# fmc.net
KiCad netlist of a schematic drawn in EAGLE
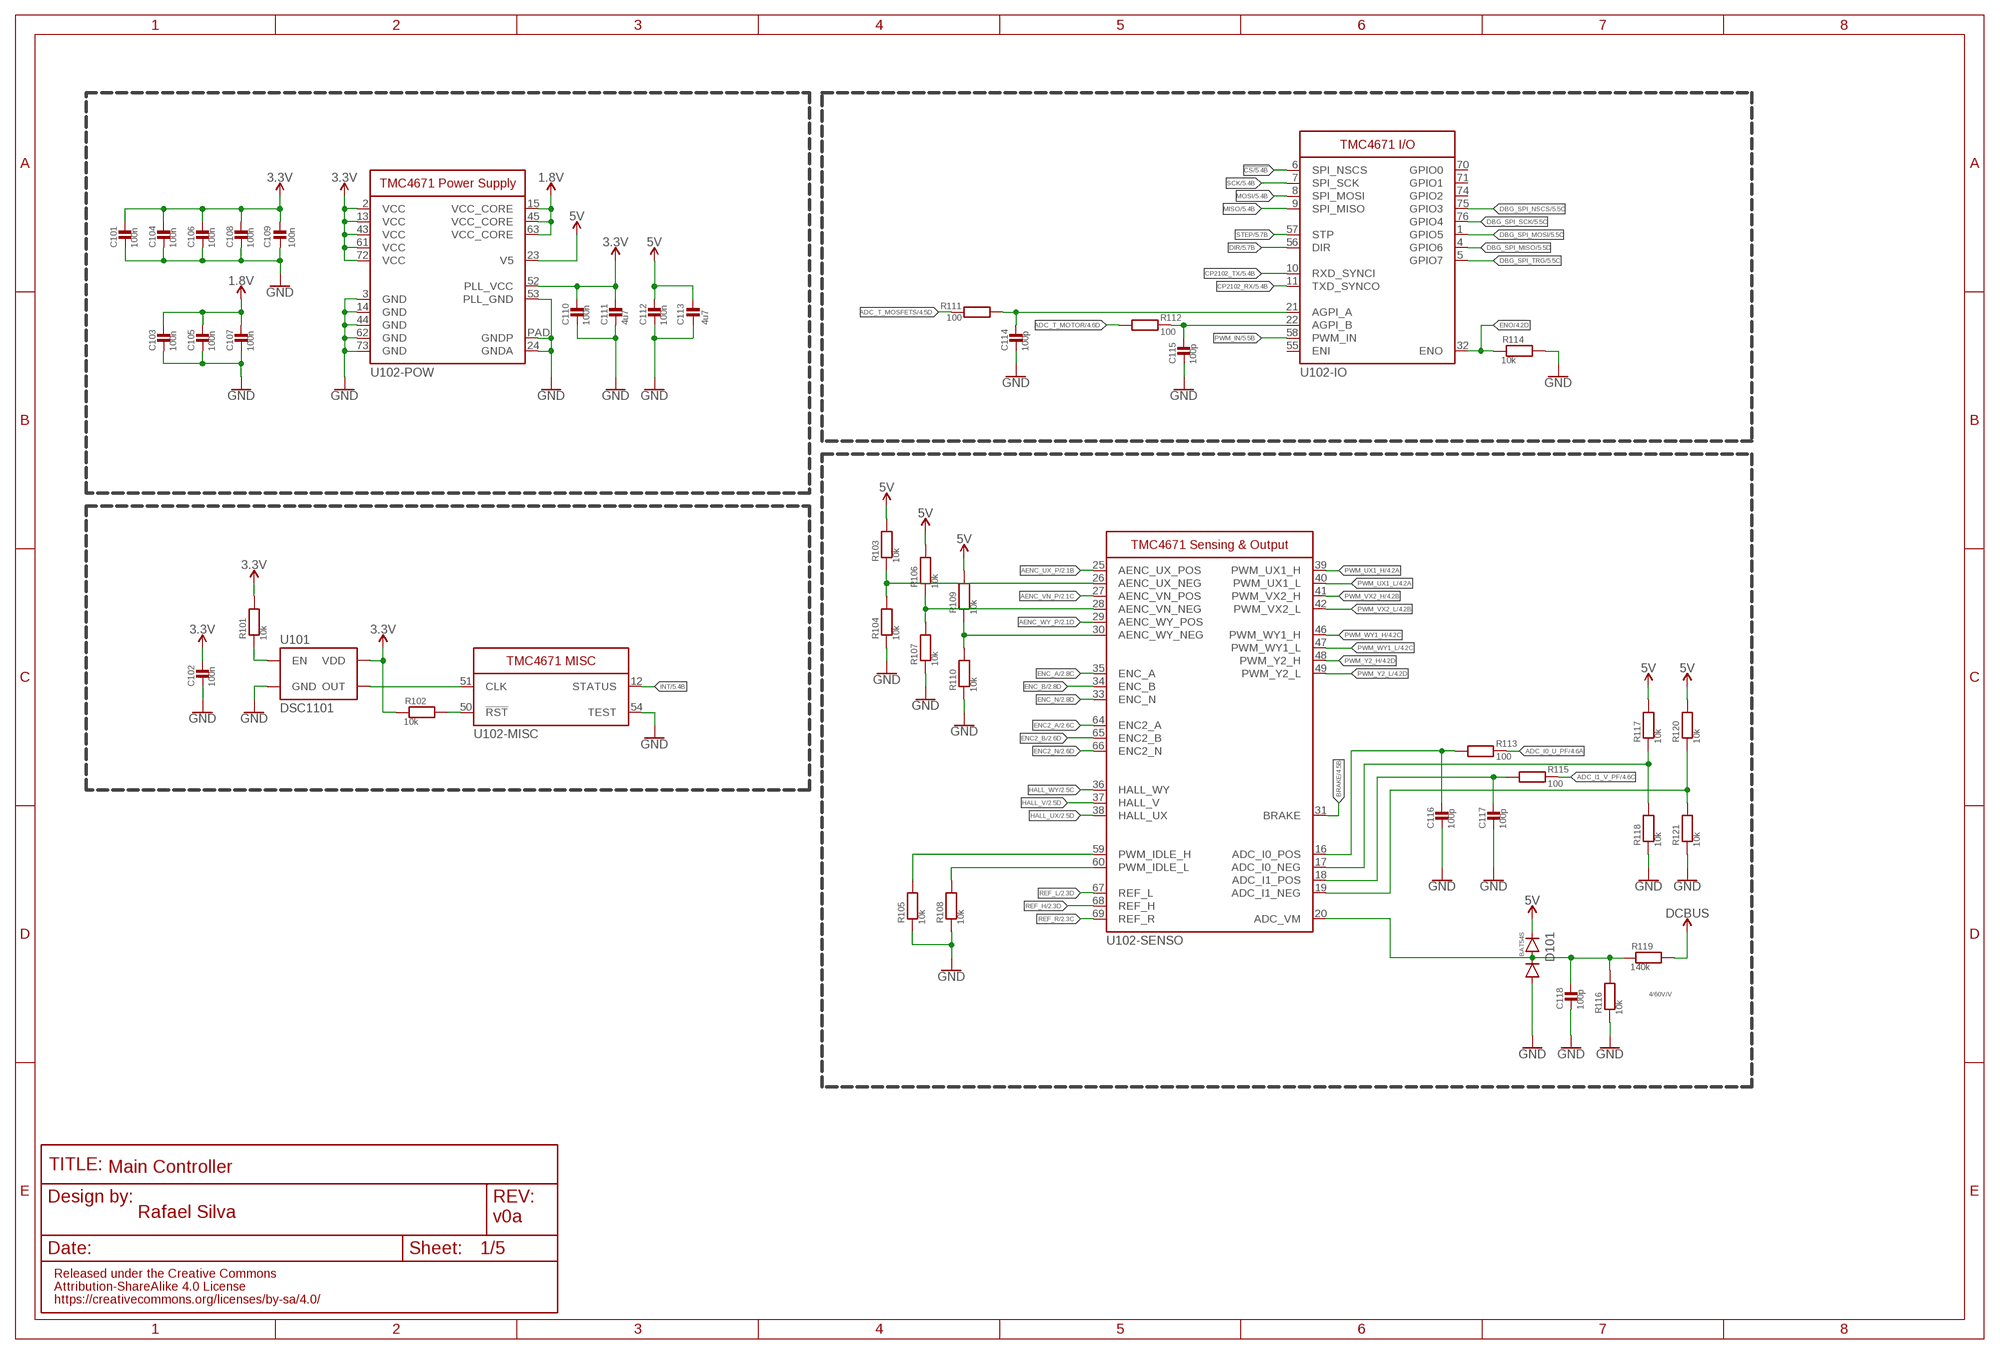
[diagram p0: schematic, sheet 1]
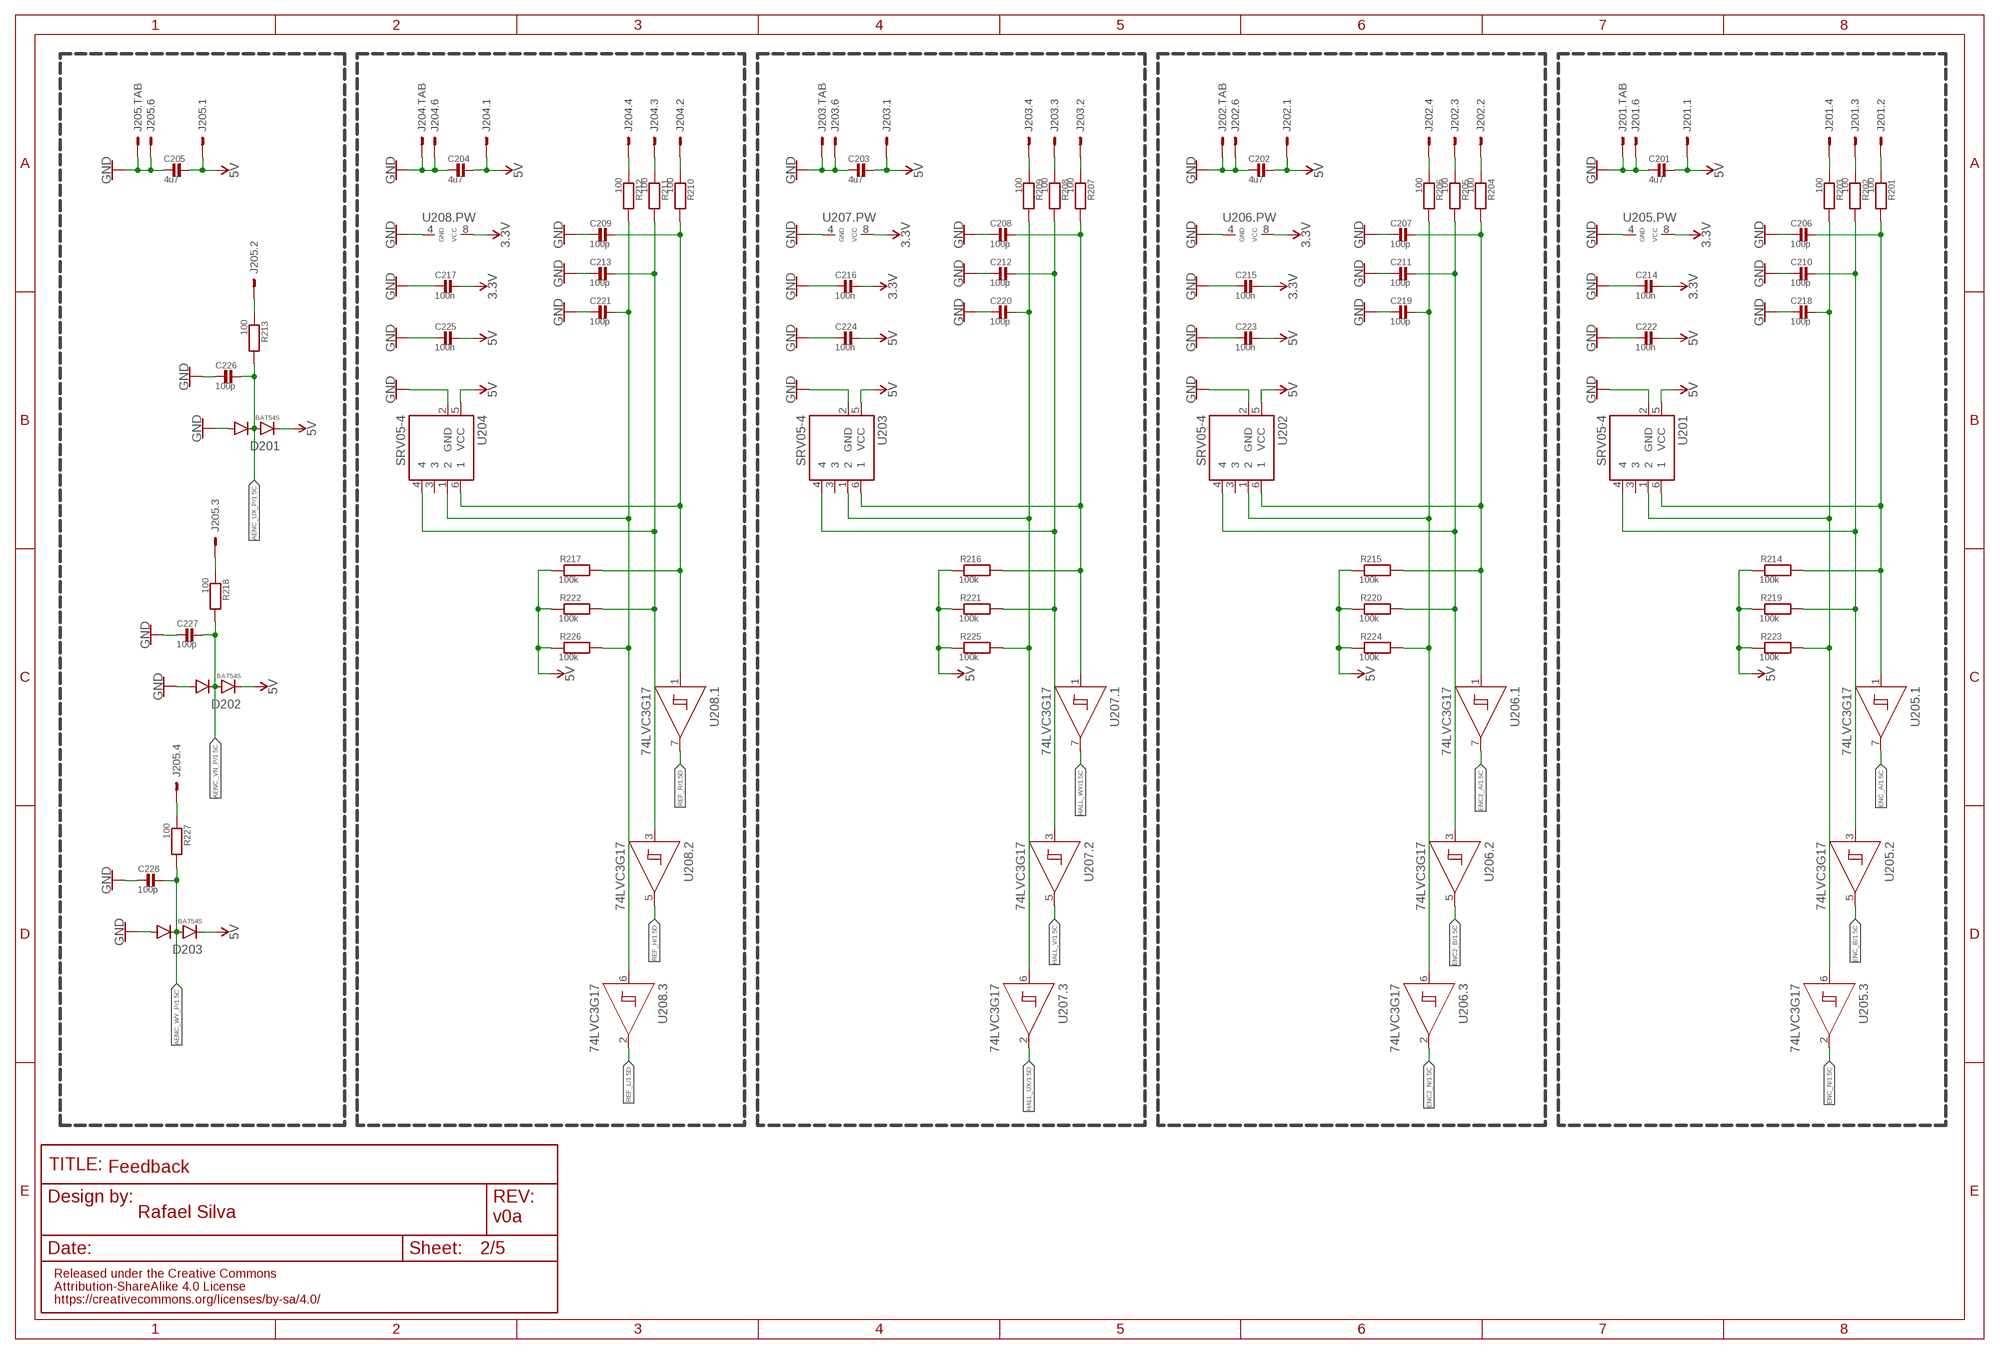
[diagram p1: schematic, sheet 2]
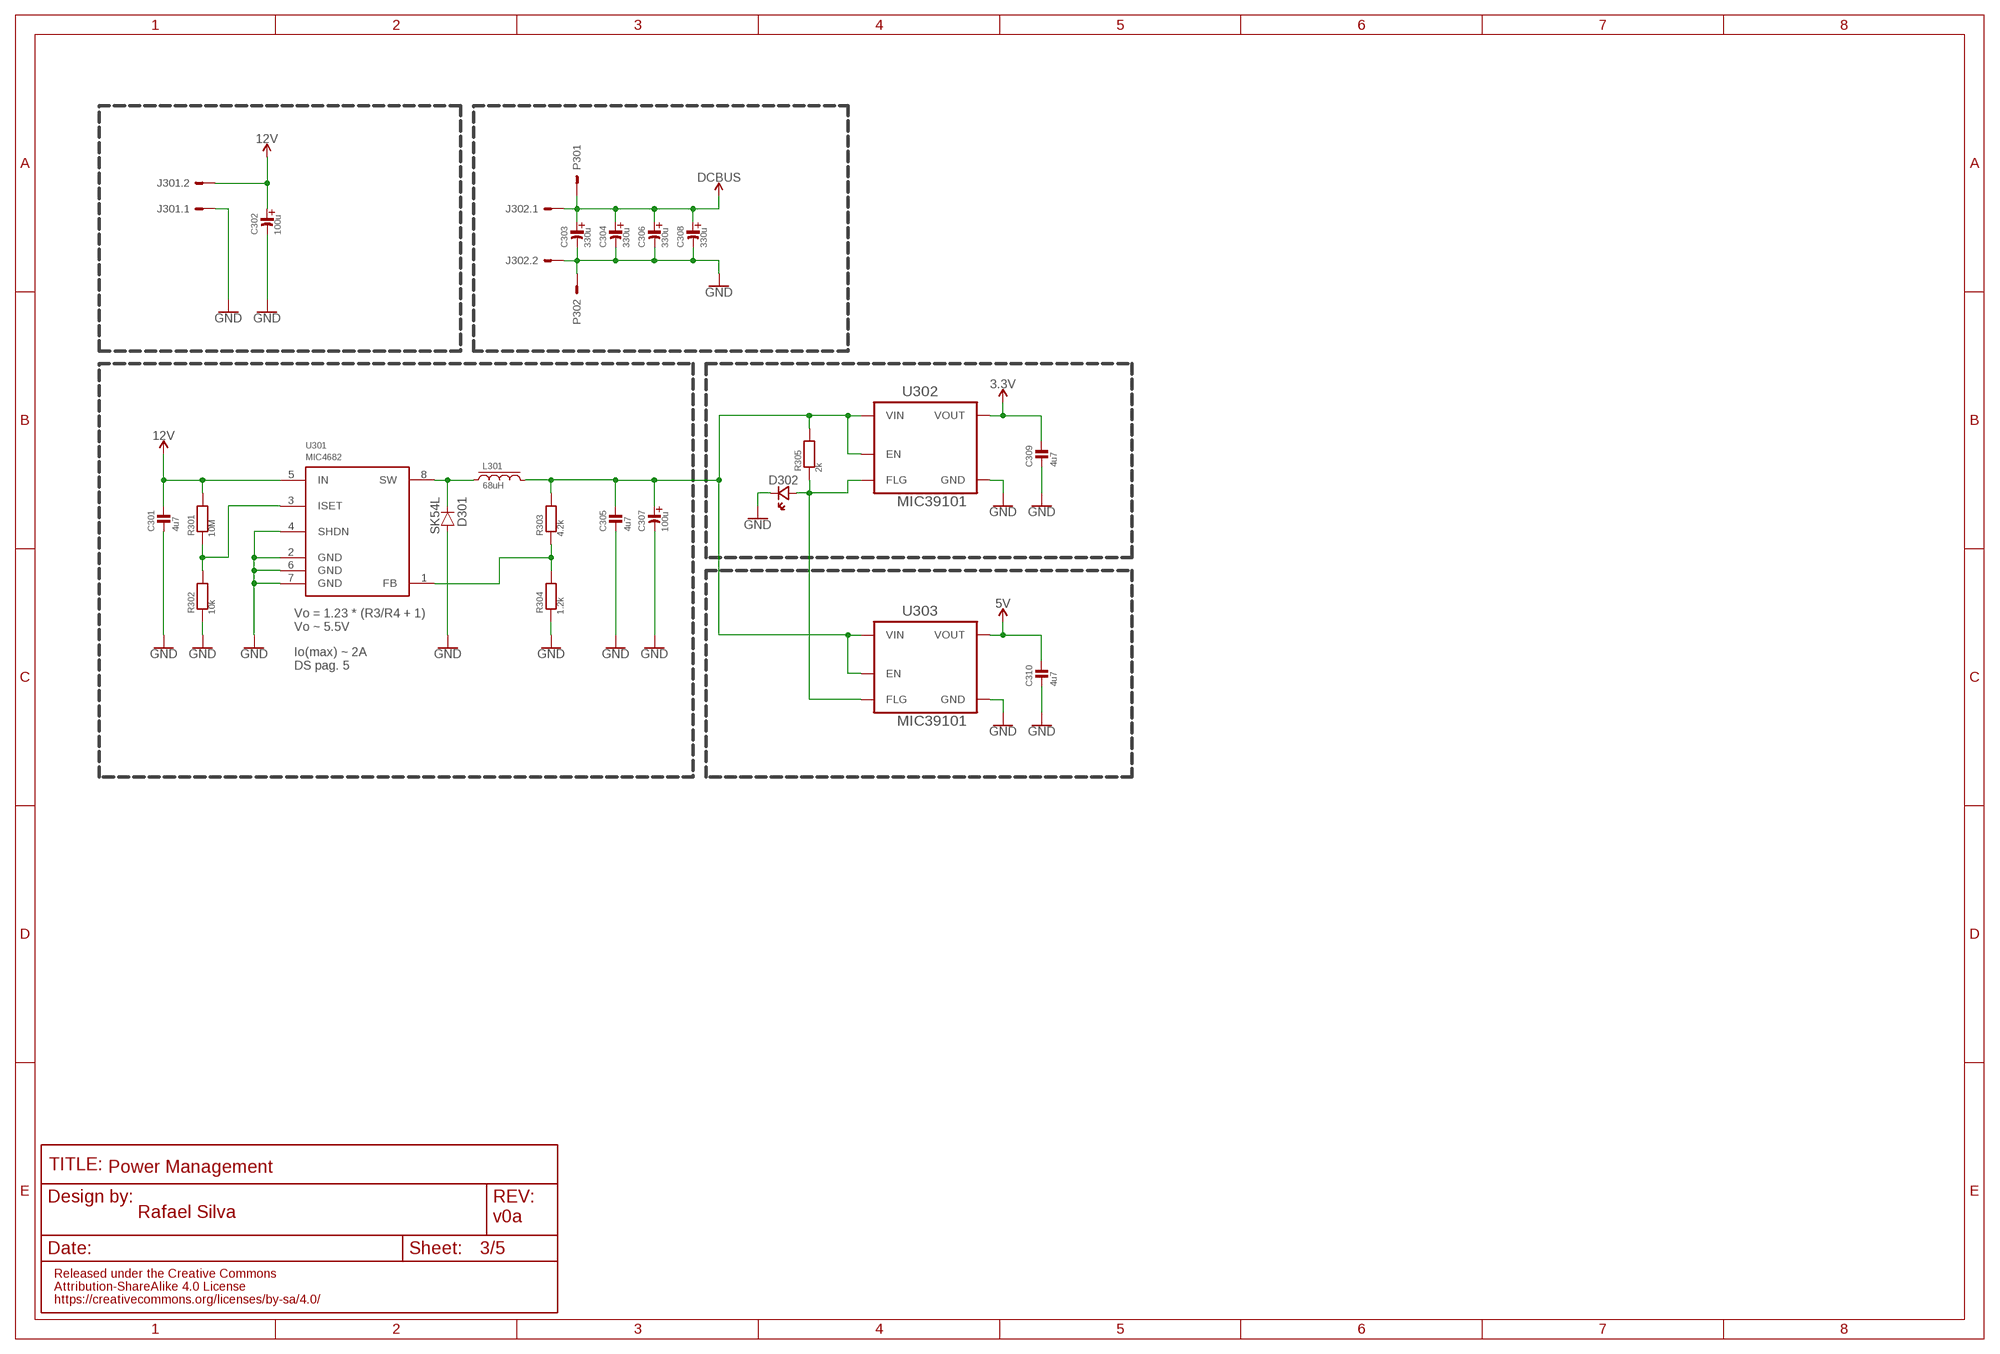
[diagram p2: schematic, sheet 3]
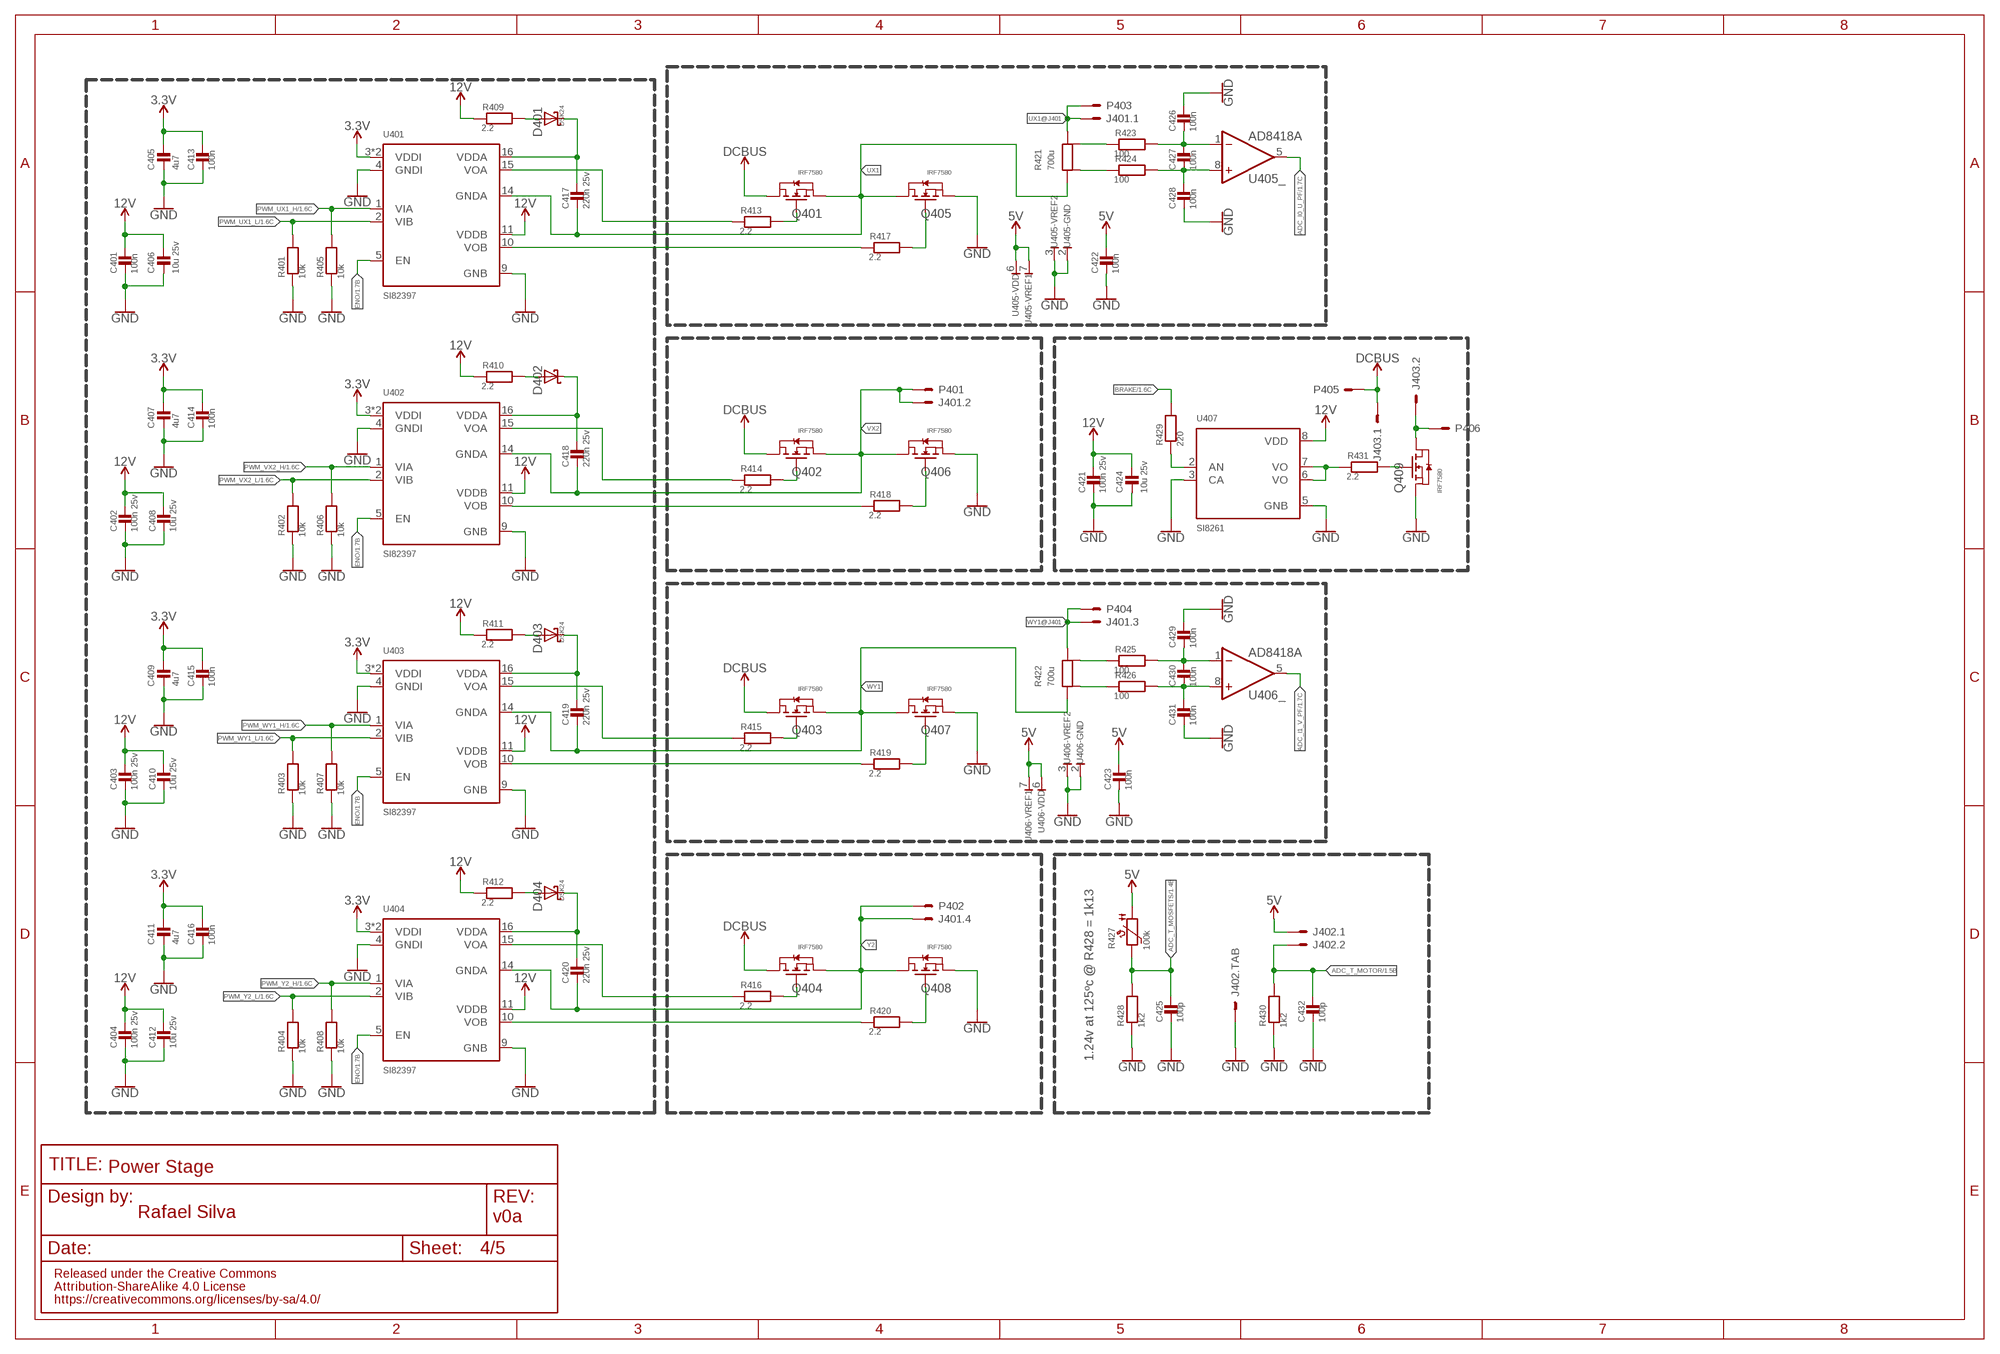
[diagram p3: schematic, sheet 4]
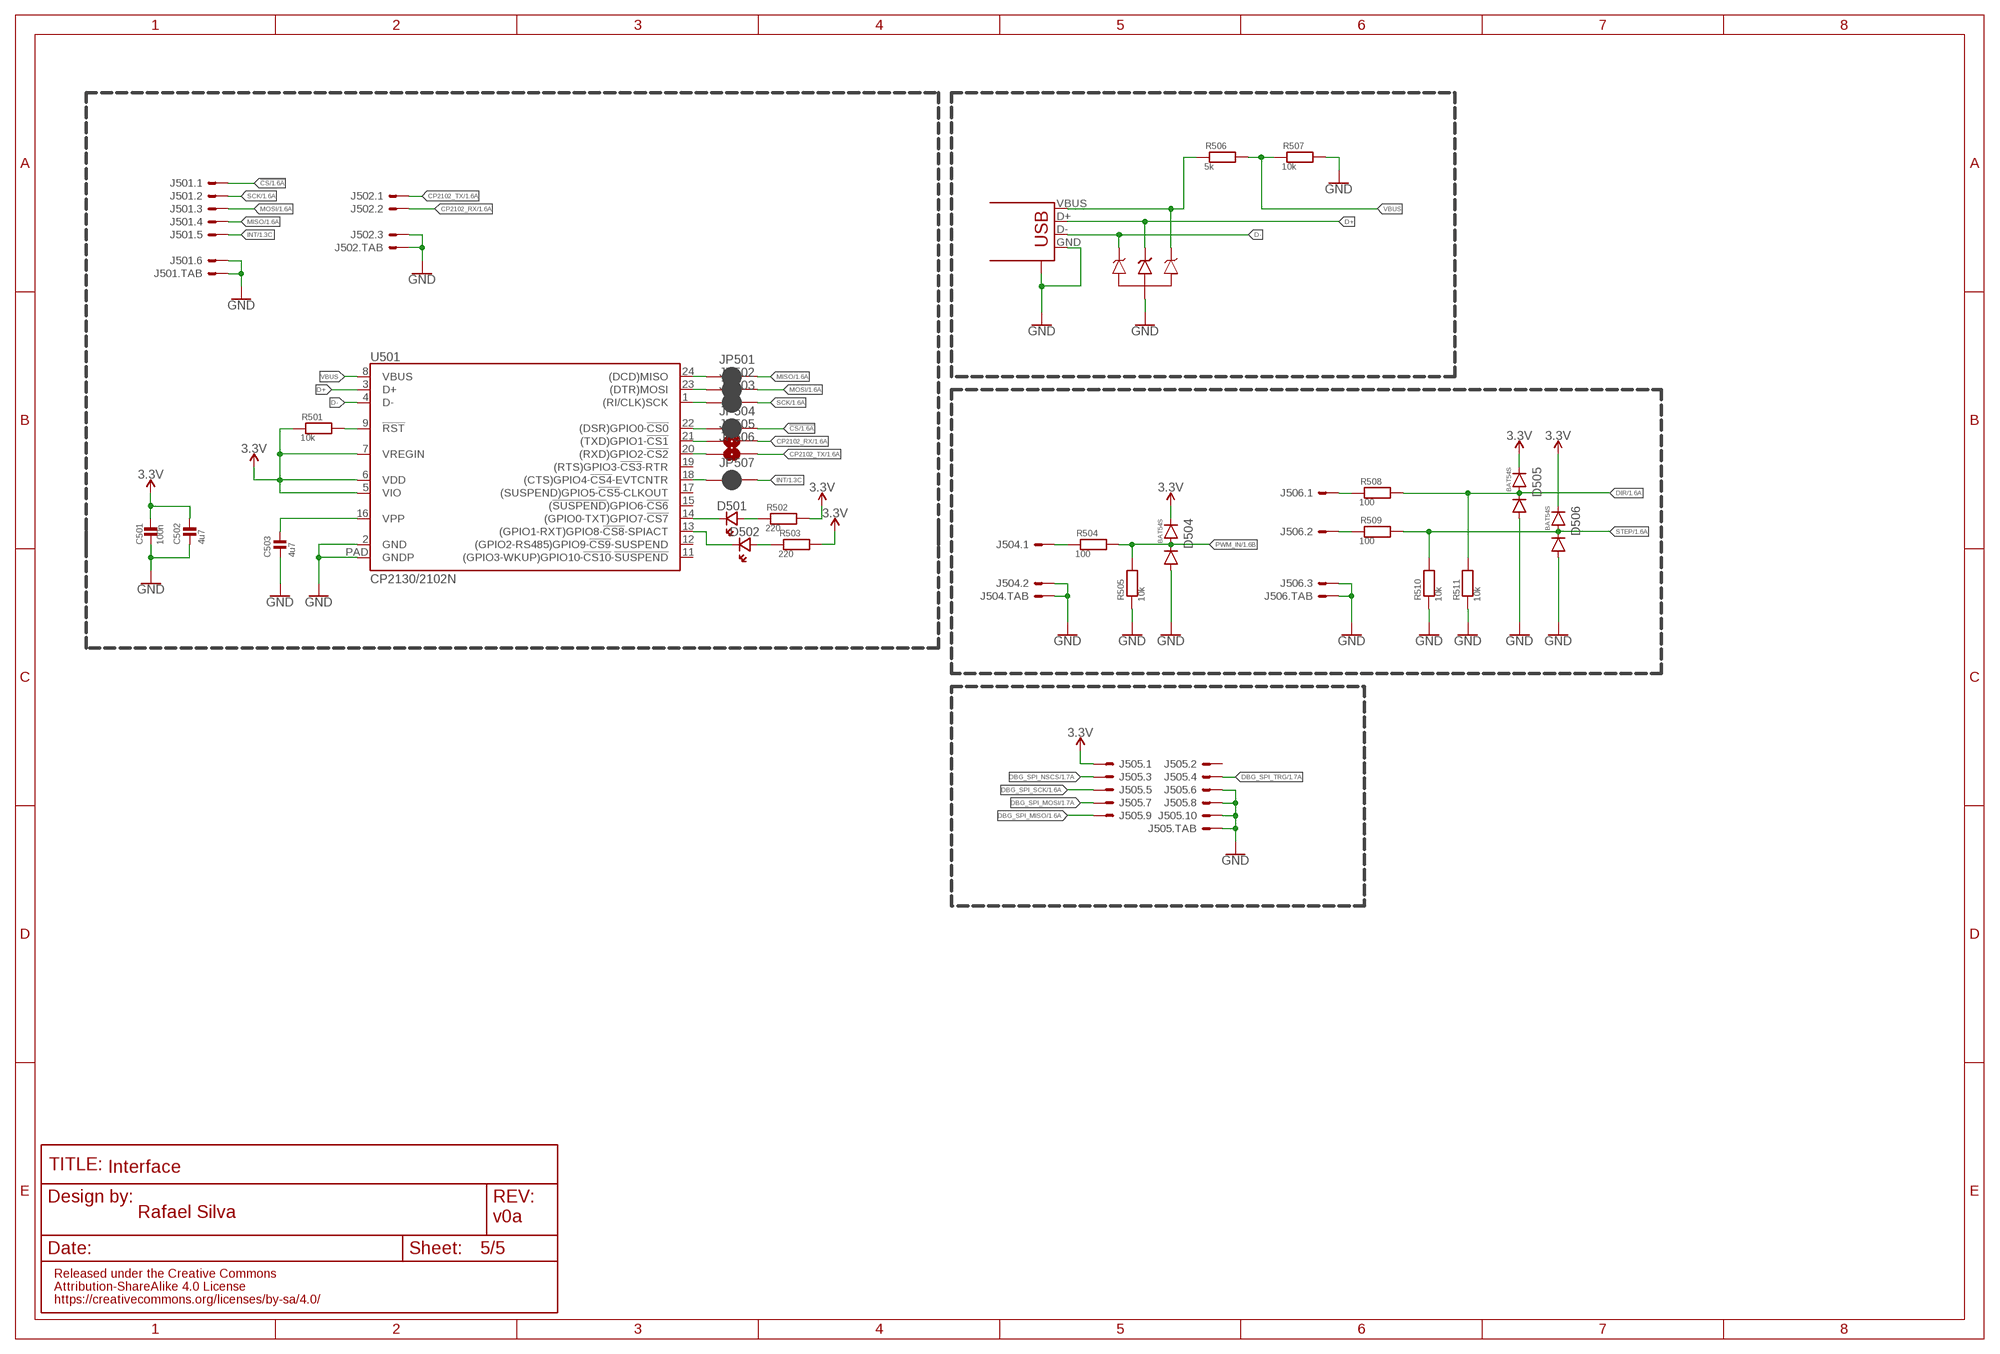
[diagram p4: schematic, sheet 5]

(export (version "E")
  (design (tool "Eeschema 10.0.6"))
  (components
    (comp (ref "C101")
      (value "100n")
      (footprint "eagle-import:0603_WAVE")
      (libsource (lib "eagle-import") (part "MLCC0603"))
    )
    (comp (ref "C102")
      (value "100n")
      (footprint "eagle-import:0603_WAVE")
      (libsource (lib "eagle-import") (part "MLCC0603"))
    )
    (comp (ref "C103")
      (value "100n")
      (footprint "eagle-import:0603_WAVE")
      (libsource (lib "eagle-import") (part "MLCC0603"))
    )
    (comp (ref "C104")
      (value "100n")
      (footprint "eagle-import:0603_WAVE")
      (libsource (lib "eagle-import") (part "MLCC0603"))
    )
    (comp (ref "C105")
      (value "100n")
      (footprint "eagle-import:0603_WAVE")
      (libsource (lib "eagle-import") (part "MLCC0603"))
    )
    (comp (ref "C106")
      (value "100n")
      (footprint "eagle-import:0603_WAVE")
      (libsource (lib "eagle-import") (part "MLCC0603"))
    )
    (comp (ref "C107")
      (value "100n")
      (footprint "eagle-import:0603_WAVE")
      (libsource (lib "eagle-import") (part "MLCC0603"))
    )
    (comp (ref "C108")
      (value "100n")
      (footprint "eagle-import:0603_WAVE")
      (libsource (lib "eagle-import") (part "MLCC0603"))
    )
    (comp (ref "C109")
      (value "100n")
      (footprint "eagle-import:0603_WAVE")
      (libsource (lib "eagle-import") (part "MLCC0603"))
    )
    (comp (ref "C110")
      (value "100n")
      (footprint "eagle-import:0603_WAVE")
      (libsource (lib "eagle-import") (part "MLCC0603"))
    )
    (comp (ref "C111")
      (value "4u7")
      (footprint "eagle-import:0603_WAVE")
      (libsource (lib "eagle-import") (part "MLCC0603"))
    )
    (comp (ref "C112")
      (value "100n")
      (footprint "eagle-import:0603_WAVE")
      (libsource (lib "eagle-import") (part "MLCC0603"))
    )
    (comp (ref "C113")
      (value "4u7")
      (footprint "eagle-import:0603_WAVE")
      (libsource (lib "eagle-import") (part "MLCC0603"))
    )
    (comp (ref "C114")
      (value "100p")
      (footprint "eagle-import:0603_WAVE")
      (libsource (lib "eagle-import") (part "MLCC0603"))
    )
    (comp (ref "C115")
      (value "100p")
      (footprint "eagle-import:0603_WAVE")
      (libsource (lib "eagle-import") (part "MLCC0603"))
    )
    (comp (ref "C116")
      (value "100p")
      (footprint "eagle-import:0603_WAVE")
      (libsource (lib "eagle-import") (part "MLCC0603"))
    )
    (comp (ref "C117")
      (value "100p")
      (footprint "eagle-import:0603_WAVE")
      (libsource (lib "eagle-import") (part "MLCC0603"))
    )
    (comp (ref "C118")
      (value "100p")
      (footprint "eagle-import:0603_WAVE")
      (libsource (lib "eagle-import") (part "MLCC0603"))
    )
    (comp (ref "D101")
      (value "BAT54S")
      (footprint "eagle-import:SOT-23-3")
      (libsource (lib "eagle-import") (part "BAT54S"))
    )
    (comp (ref "R101")
      (value "10k")
      (footprint "eagle-import:0603_WAVE")
      (libsource (lib "eagle-import") (part "RESISTOR0603"))
    )
    (comp (ref "R102")
      (value "10k")
      (footprint "eagle-import:0603_WAVE")
      (libsource (lib "eagle-import") (part "RESISTOR0603"))
    )
    (comp (ref "R103")
      (value "10k")
      (footprint "eagle-import:0603_WAVE")
      (libsource (lib "eagle-import") (part "RESISTOR0603"))
    )
    (comp (ref "R104")
      (value "10k")
      (footprint "eagle-import:0603_WAVE")
      (libsource (lib "eagle-import") (part "RESISTOR0603"))
    )
    (comp (ref "R105")
      (value "10k")
      (footprint "eagle-import:0603_WAVE")
      (libsource (lib "eagle-import") (part "RESISTOR0603"))
    )
    (comp (ref "R106")
      (value "10k")
      (footprint "eagle-import:0603_WAVE")
      (libsource (lib "eagle-import") (part "RESISTOR0603"))
    )
    (comp (ref "R107")
      (value "10k")
      (footprint "eagle-import:0603_WAVE")
      (libsource (lib "eagle-import") (part "RESISTOR0603"))
    )
    (comp (ref "R108")
      (value "10k")
      (footprint "eagle-import:0603_WAVE")
      (libsource (lib "eagle-import") (part "RESISTOR0603"))
    )
    (comp (ref "R109")
      (value "10k")
      (footprint "eagle-import:0603_WAVE")
      (libsource (lib "eagle-import") (part "RESISTOR0603"))
    )
    (comp (ref "R110")
      (value "10k")
      (footprint "eagle-import:0603_WAVE")
      (libsource (lib "eagle-import") (part "RESISTOR0603"))
    )
    (comp (ref "R111")
      (value "100")
      (footprint "eagle-import:0603_WAVE")
      (libsource (lib "eagle-import") (part "RESISTOR0603"))
    )
    (comp (ref "R112")
      (value "100")
      (footprint "eagle-import:0603_WAVE")
      (libsource (lib "eagle-import") (part "RESISTOR0603"))
    )
    (comp (ref "R113")
      (value "100")
      (footprint "eagle-import:0603_WAVE")
      (libsource (lib "eagle-import") (part "RESISTOR0603"))
    )
    (comp (ref "R114")
      (value "10k")
      (footprint "eagle-import:0603_WAVE")
      (libsource (lib "eagle-import") (part "RESISTOR0603"))
    )
    (comp (ref "R115")
      (value "100")
      (footprint "eagle-import:0603_WAVE")
      (libsource (lib "eagle-import") (part "RESISTOR0603"))
    )
    (comp (ref "R116")
      (value "10k")
      (footprint "eagle-import:0603_WAVE")
      (libsource (lib "eagle-import") (part "RESISTOR0603"))
    )
    (comp (ref "R117")
      (value "10k")
      (footprint "eagle-import:0603_WAVE")
      (libsource (lib "eagle-import") (part "RESISTOR0603"))
    )
    (comp (ref "R118")
      (value "10k")
      (footprint "eagle-import:0603_WAVE")
      (libsource (lib "eagle-import") (part "RESISTOR0603"))
    )
    (comp (ref "R119")
      (value "140k")
      (footprint "eagle-import:0603_WAVE")
      (libsource (lib "eagle-import") (part "RESISTOR0603"))
    )
    (comp (ref "R120")
      (value "10k")
      (footprint "eagle-import:0603_WAVE")
      (libsource (lib "eagle-import") (part "RESISTOR0603"))
    )
    (comp (ref "R121")
      (value "10k")
      (footprint "eagle-import:0603_WAVE")
      (libsource (lib "eagle-import") (part "RESISTOR0603"))
    )
    (comp (ref "U101")
      (value "DSC1101")
      (footprint "eagle-import:CDFN_5X3.2")
      (libsource (lib "eagle-import") (part "DSC1101"))
    )
    (comp (ref "U102")
      (value "TMC4671")
      (footprint "eagle-import:QFN76")
      (libsource (lib "eagle-import") (part "TMC4671"))
    )
    (comp (ref "C501")
      (value "100n")
      (footprint "eagle-import:0603_WAVE")
      (libsource (lib "eagle-import") (part "MLCC0603"))
    )
    (comp (ref "C502")
      (value "4u7")
      (footprint "eagle-import:0603_WAVE")
      (libsource (lib "eagle-import") (part "MLCC0603"))
    )
    (comp (ref "C503")
      (value "4u7")
      (footprint "eagle-import:0603_WAVE")
      (libsource (lib "eagle-import") (part "MLCC0603"))
    )
    (comp (ref "D501")
      (value "LED0603")
      (footprint "eagle-import:CHIPLED_0603")
      (libsource (lib "eagle-import") (part "LED0603"))
    )
    (comp (ref "D502")
      (value "LED0603")
      (footprint "eagle-import:CHIPLED_0603")
      (libsource (lib "eagle-import") (part "LED0603"))
    )
    (comp (ref "D503")
      (value "SP0503BAHT")
      (footprint "eagle-import:SOT143")
      (libsource (lib "eagle-import") (part "SP0503BAHT"))
    )
    (comp (ref "D504")
      (value "BAT54S")
      (footprint "eagle-import:SOT-23-3")
      (libsource (lib "eagle-import") (part "BAT54S"))
    )
    (comp (ref "D505")
      (value "BAT54S")
      (footprint "eagle-import:SOT-23-3")
      (libsource (lib "eagle-import") (part "BAT54S"))
    )
    (comp (ref "D506")
      (value "BAT54S")
      (footprint "eagle-import:SOT-23-3")
      (libsource (lib "eagle-import") (part "BAT54S"))
    )
    (comp (ref "J501")
      (value "SH-6")
      (footprint "eagle-import:SM06B-SSR-H-TB")
      (libsource (lib "eagle-import") (part "SH-6"))
    )
    (comp (ref "J502")
      (value "SH-3")
      (footprint "eagle-import:SM03B-SSR-H-TB")
      (libsource (lib "eagle-import") (part "SH-3"))
    )
    (comp (ref "J503")
      (value "USB-SHIELD")
      (footprint "eagle-import:USB-M-S1")
      (libsource (lib "eagle-import") (part "USB-SHIELD"))
    )
    (comp (ref "J504")
      (value "SH-2")
      (footprint "eagle-import:SM02B-SSR-H-TB")
      (libsource (lib "eagle-import") (part "SH-2"))
    )
    (comp (ref "J505")
      (value "F20F-10DP-1V")
      (footprint "eagle-import:F20F-10DP-1V")
      (libsource (lib "eagle-import") (part "F20F-10DP-1V"))
    )
    (comp (ref "J506")
      (value "SH-3")
      (footprint "eagle-import:SM03B-SSR-H-TB")
      (libsource (lib "eagle-import") (part "SH-3"))
    )
    (comp (ref "JP501")
      (value "JUMPER-SMT_2_NC_PASTE_SILK")
      (footprint "eagle-import:SMT-JUMPER_2_NC_PASTE_SILK")
      (libsource (lib "eagle-import") (part "JUMPER-SMT_2_NC_PASTE_SILK"))
    )
    (comp (ref "JP502")
      (value "JUMPER-SMT_2_NC_PASTE_SILK")
      (footprint "eagle-import:SMT-JUMPER_2_NC_PASTE_SILK")
      (libsource (lib "eagle-import") (part "JUMPER-SMT_2_NC_PASTE_SILK"))
    )
    (comp (ref "JP503")
      (value "JUMPER-SMT_2_NC_PASTE_SILK")
      (footprint "eagle-import:SMT-JUMPER_2_NC_PASTE_SILK")
      (libsource (lib "eagle-import") (part "JUMPER-SMT_2_NC_PASTE_SILK"))
    )
    (comp (ref "JP504")
      (value "JUMPER-SMT_2_NC_PASTE_SILK")
      (footprint "eagle-import:SMT-JUMPER_2_NC_PASTE_SILK")
      (libsource (lib "eagle-import") (part "JUMPER-SMT_2_NC_PASTE_SILK"))
    )
    (comp (ref "JP505")
      (value "JUMPER-SMT_2_NO_SILK")
      (footprint "eagle-import:SMT-JUMPER_2_NO_SILK")
      (libsource (lib "eagle-import") (part "JUMPER-SMT_2_NO_SILK"))
    )
    (comp (ref "JP506")
      (value "JUMPER-SMT_2_NO_SILK")
      (footprint "eagle-import:SMT-JUMPER_2_NO_SILK")
      (libsource (lib "eagle-import") (part "JUMPER-SMT_2_NO_SILK"))
    )
    (comp (ref "JP507")
      (value "JUMPER-SMT_2_NC_PASTE_SILK")
      (footprint "eagle-import:SMT-JUMPER_2_NC_PASTE_SILK")
      (libsource (lib "eagle-import") (part "JUMPER-SMT_2_NC_PASTE_SILK"))
    )
    (comp (ref "R501")
      (value "10k")
      (footprint "eagle-import:0603_WAVE")
      (libsource (lib "eagle-import") (part "RESISTOR0603"))
    )
    (comp (ref "R502")
      (value "220")
      (footprint "eagle-import:0603_WAVE")
      (libsource (lib "eagle-import") (part "RESISTOR0603"))
    )
    (comp (ref "R503")
      (value "220")
      (footprint "eagle-import:0603_WAVE")
      (libsource (lib "eagle-import") (part "RESISTOR0603"))
    )
    (comp (ref "R504")
      (value "100")
      (footprint "eagle-import:0603_WAVE")
      (libsource (lib "eagle-import") (part "RESISTOR0603"))
    )
    (comp (ref "R505")
      (value "10k")
      (footprint "eagle-import:0603_WAVE")
      (libsource (lib "eagle-import") (part "RESISTOR0603"))
    )
    (comp (ref "R506")
      (value "5k")
      (footprint "eagle-import:0603_WAVE")
      (libsource (lib "eagle-import") (part "RESISTOR0603"))
    )
    (comp (ref "R507")
      (value "10k")
      (footprint "eagle-import:0603_WAVE")
      (libsource (lib "eagle-import") (part "RESISTOR0603"))
    )
    (comp (ref "R508")
      (value "100")
      (footprint "eagle-import:0603_WAVE")
      (libsource (lib "eagle-import") (part "RESISTOR0603"))
    )
    (comp (ref "R509")
      (value "100")
      (footprint "eagle-import:0603_WAVE")
      (libsource (lib "eagle-import") (part "RESISTOR0603"))
    )
    (comp (ref "R510")
      (value "10k")
      (footprint "eagle-import:0603_WAVE")
      (libsource (lib "eagle-import") (part "RESISTOR0603"))
    )
    (comp (ref "R511")
      (value "10k")
      (footprint "eagle-import:0603_WAVE")
      (libsource (lib "eagle-import") (part "RESISTOR0603"))
    )
    (comp (ref "U501")
      (value "CP2130/2102N")
      (footprint "eagle-import:QFN24")
      (libsource (lib "eagle-import") (part "CP2130/2102N"))
    )
    (comp (ref "C201")
      (value "4u7")
      (footprint "eagle-import:0603_WAVE")
      (libsource (lib "eagle-import") (part "MLCC0603"))
    )
    (comp (ref "C202")
      (value "4u7")
      (footprint "eagle-import:0603_WAVE")
      (libsource (lib "eagle-import") (part "MLCC0603"))
    )
    (comp (ref "C203")
      (value "4u7")
      (footprint "eagle-import:0603_WAVE")
      (libsource (lib "eagle-import") (part "MLCC0603"))
    )
    (comp (ref "C204")
      (value "4u7")
      (footprint "eagle-import:0603_WAVE")
      (libsource (lib "eagle-import") (part "MLCC0603"))
    )
    (comp (ref "C205")
      (value "4u7")
      (footprint "eagle-import:0603_WAVE")
      (libsource (lib "eagle-import") (part "MLCC0603"))
    )
    (comp (ref "C206")
      (value "100p")
      (footprint "eagle-import:0603_WAVE")
      (libsource (lib "eagle-import") (part "MLCC0603"))
    )
    (comp (ref "C207")
      (value "100p")
      (footprint "eagle-import:0603_WAVE")
      (libsource (lib "eagle-import") (part "MLCC0603"))
    )
    (comp (ref "C208")
      (value "100p")
      (footprint "eagle-import:0603_WAVE")
      (libsource (lib "eagle-import") (part "MLCC0603"))
    )
    (comp (ref "C209")
      (value "100p")
      (footprint "eagle-import:0603_WAVE")
      (libsource (lib "eagle-import") (part "MLCC0603"))
    )
    (comp (ref "C210")
      (value "100p")
      (footprint "eagle-import:0603_WAVE")
      (libsource (lib "eagle-import") (part "MLCC0603"))
    )
    (comp (ref "C211")
      (value "100p")
      (footprint "eagle-import:0603_WAVE")
      (libsource (lib "eagle-import") (part "MLCC0603"))
    )
    (comp (ref "C212")
      (value "100p")
      (footprint "eagle-import:0603_WAVE")
      (libsource (lib "eagle-import") (part "MLCC0603"))
    )
    (comp (ref "C213")
      (value "100p")
      (footprint "eagle-import:0603_WAVE")
      (libsource (lib "eagle-import") (part "MLCC0603"))
    )
    (comp (ref "C214")
      (value "100n")
      (footprint "eagle-import:0603_WAVE")
      (libsource (lib "eagle-import") (part "MLCC0603"))
    )
    (comp (ref "C215")
      (value "100n")
      (footprint "eagle-import:0603_WAVE")
      (libsource (lib "eagle-import") (part "MLCC0603"))
    )
    (comp (ref "C216")
      (value "100n")
      (footprint "eagle-import:0603_WAVE")
      (libsource (lib "eagle-import") (part "MLCC0603"))
    )
    (comp (ref "C217")
      (value "100n")
      (footprint "eagle-import:0603_WAVE")
      (libsource (lib "eagle-import") (part "MLCC0603"))
    )
    (comp (ref "C218")
      (value "100p")
      (footprint "eagle-import:0603_WAVE")
      (libsource (lib "eagle-import") (part "MLCC0603"))
    )
    (comp (ref "C219")
      (value "100p")
      (footprint "eagle-import:0603_WAVE")
      (libsource (lib "eagle-import") (part "MLCC0603"))
    )
    (comp (ref "C220")
      (value "100p")
      (footprint "eagle-import:0603_WAVE")
      (libsource (lib "eagle-import") (part "MLCC0603"))
    )
    (comp (ref "C221")
      (value "100p")
      (footprint "eagle-import:0603_WAVE")
      (libsource (lib "eagle-import") (part "MLCC0603"))
    )
    (comp (ref "C222")
      (value "100n")
      (footprint "eagle-import:0603_WAVE")
      (libsource (lib "eagle-import") (part "MLCC0603"))
    )
    (comp (ref "C223")
      (value "100n")
      (footprint "eagle-import:0603_WAVE")
      (libsource (lib "eagle-import") (part "MLCC0603"))
    )
    (comp (ref "C224")
      (value "100n")
      (footprint "eagle-import:0603_WAVE")
      (libsource (lib "eagle-import") (part "MLCC0603"))
    )
    (comp (ref "C225")
      (value "100n")
      (footprint "eagle-import:0603_WAVE")
      (libsource (lib "eagle-import") (part "MLCC0603"))
    )
    (comp (ref "C226")
      (value "100p")
      (footprint "eagle-import:0603_WAVE")
      (libsource (lib "eagle-import") (part "MLCC0603"))
    )
    (comp (ref "C227")
      (value "100p")
      (footprint "eagle-import:0603_WAVE")
      (libsource (lib "eagle-import") (part "MLCC0603"))
    )
    (comp (ref "C228")
      (value "100p")
      (footprint "eagle-import:0603_WAVE")
      (libsource (lib "eagle-import") (part "MLCC0603"))
    )
    (comp (ref "D201")
      (value "BAT54S")
      (footprint "eagle-import:SOT-23-3")
      (libsource (lib "eagle-import") (part "BAT54S"))
    )
    (comp (ref "D202")
      (value "BAT54S")
      (footprint "eagle-import:SOT-23-3")
      (libsource (lib "eagle-import") (part "BAT54S"))
    )
    (comp (ref "D203")
      (value "BAT54S")
      (footprint "eagle-import:SOT-23-3")
      (libsource (lib "eagle-import") (part "BAT54S"))
    )
    (comp (ref "J201")
      (value "SH-5")
      (footprint "eagle-import:SM05B-SSR-H-TB")
      (libsource (lib "eagle-import") (part "SH-5"))
    )
    (comp (ref "J202")
      (value "SH-5")
      (footprint "eagle-import:SM05B-SSR-H-TB")
      (libsource (lib "eagle-import") (part "SH-5"))
    )
    (comp (ref "J203")
      (value "SH-5")
      (footprint "eagle-import:SM05B-SSR-H-TB")
      (libsource (lib "eagle-import") (part "SH-5"))
    )
    (comp (ref "J204")
      (value "SH-5")
      (footprint "eagle-import:SM05B-SSR-H-TB")
      (libsource (lib "eagle-import") (part "SH-5"))
    )
    (comp (ref "J205")
      (value "SH-5")
      (footprint "eagle-import:SM05B-SSR-H-TB")
      (libsource (lib "eagle-import") (part "SH-5"))
    )
    (comp (ref "R201")
      (value "100")
      (footprint "eagle-import:0603_WAVE")
      (libsource (lib "eagle-import") (part "RESISTOR0603"))
    )
    (comp (ref "R202")
      (value "100")
      (footprint "eagle-import:0603_WAVE")
      (libsource (lib "eagle-import") (part "RESISTOR0603"))
    )
    (comp (ref "R203")
      (value "100")
      (footprint "eagle-import:0603_WAVE")
      (libsource (lib "eagle-import") (part "RESISTOR0603"))
    )
    (comp (ref "R204")
      (value "100")
      (footprint "eagle-import:0603_WAVE")
      (libsource (lib "eagle-import") (part "RESISTOR0603"))
    )
    (comp (ref "R205")
      (value "100")
      (footprint "eagle-import:0603_WAVE")
      (libsource (lib "eagle-import") (part "RESISTOR0603"))
    )
    (comp (ref "R206")
      (value "100")
      (footprint "eagle-import:0603_WAVE")
      (libsource (lib "eagle-import") (part "RESISTOR0603"))
    )
    (comp (ref "R207")
      (value "100")
      (footprint "eagle-import:0603_WAVE")
      (libsource (lib "eagle-import") (part "RESISTOR0603"))
    )
    (comp (ref "R208")
      (value "100")
      (footprint "eagle-import:0603_WAVE")
      (libsource (lib "eagle-import") (part "RESISTOR0603"))
    )
    (comp (ref "R209")
      (value "100")
      (footprint "eagle-import:0603_WAVE")
      (libsource (lib "eagle-import") (part "RESISTOR0603"))
    )
    (comp (ref "R210")
      (value "100")
      (footprint "eagle-import:0603_WAVE")
      (libsource (lib "eagle-import") (part "RESISTOR0603"))
    )
    (comp (ref "R211")
      (value "100")
      (footprint "eagle-import:0603_WAVE")
      (libsource (lib "eagle-import") (part "RESISTOR0603"))
    )
    (comp (ref "R212")
      (value "100")
      (footprint "eagle-import:0603_WAVE")
      (libsource (lib "eagle-import") (part "RESISTOR0603"))
    )
    (comp (ref "R213")
      (value "100")
      (footprint "eagle-import:0603_WAVE")
      (libsource (lib "eagle-import") (part "RESISTOR0603"))
    )
    (comp (ref "R214")
      (value "100k")
      (footprint "eagle-import:0603_WAVE")
      (libsource (lib "eagle-import") (part "RESISTOR0603"))
    )
    (comp (ref "R215")
      (value "100k")
      (footprint "eagle-import:0603_WAVE")
      (libsource (lib "eagle-import") (part "RESISTOR0603"))
    )
    (comp (ref "R216")
      (value "100k")
      (footprint "eagle-import:0603_WAVE")
      (libsource (lib "eagle-import") (part "RESISTOR0603"))
    )
    (comp (ref "R217")
      (value "100k")
      (footprint "eagle-import:0603_WAVE")
      (libsource (lib "eagle-import") (part "RESISTOR0603"))
    )
    (comp (ref "R218")
      (value "100")
      (footprint "eagle-import:0603_WAVE")
      (libsource (lib "eagle-import") (part "RESISTOR0603"))
    )
    (comp (ref "R219")
      (value "100k")
      (footprint "eagle-import:0603_WAVE")
      (libsource (lib "eagle-import") (part "RESISTOR0603"))
    )
    (comp (ref "R220")
      (value "100k")
      (footprint "eagle-import:0603_WAVE")
      (libsource (lib "eagle-import") (part "RESISTOR0603"))
    )
    (comp (ref "R221")
      (value "100k")
      (footprint "eagle-import:0603_WAVE")
      (libsource (lib "eagle-import") (part "RESISTOR0603"))
    )
    (comp (ref "R222")
      (value "100k")
      (footprint "eagle-import:0603_WAVE")
      (libsource (lib "eagle-import") (part "RESISTOR0603"))
    )
    (comp (ref "R223")
      (value "100k")
      (footprint "eagle-import:0603_WAVE")
      (libsource (lib "eagle-import") (part "RESISTOR0603"))
    )
    (comp (ref "R224")
      (value "100k")
      (footprint "eagle-import:0603_WAVE")
      (libsource (lib "eagle-import") (part "RESISTOR0603"))
    )
    (comp (ref "R225")
      (value "100k")
      (footprint "eagle-import:0603_WAVE")
      (libsource (lib "eagle-import") (part "RESISTOR0603"))
    )
    (comp (ref "R226")
      (value "100k")
      (footprint "eagle-import:0603_WAVE")
      (libsource (lib "eagle-import") (part "RESISTOR0603"))
    )
    (comp (ref "R227")
      (value "100")
      (footprint "eagle-import:0603_WAVE")
      (libsource (lib "eagle-import") (part "RESISTOR0603"))
    )
    (comp (ref "U201")
      (value "SRV05-4")
      (footprint "eagle-import:SOT23-6")
      (libsource (lib "eagle-import") (part "SRV05-4"))
    )
    (comp (ref "U202")
      (value "SRV05-4")
      (footprint "eagle-import:SOT23-6")
      (libsource (lib "eagle-import") (part "SRV05-4"))
    )
    (comp (ref "U203")
      (value "SRV05-4")
      (footprint "eagle-import:SOT23-6")
      (libsource (lib "eagle-import") (part "SRV05-4"))
    )
    (comp (ref "U204")
      (value "SRV05-4")
      (footprint "eagle-import:SOT23-6")
      (libsource (lib "eagle-import") (part "SRV05-4"))
    )
    (comp (ref "U205")
      (value "74LVC3G17")
      (footprint "eagle-import:TSSOP-8")
      (libsource (lib "eagle-import") (part "74LVC3G17"))
    )
    (comp (ref "U206")
      (value "74LVC3G17")
      (footprint "eagle-import:TSSOP-8")
      (libsource (lib "eagle-import") (part "74LVC3G17"))
    )
    (comp (ref "U207")
      (value "74LVC3G17")
      (footprint "eagle-import:TSSOP-8")
      (libsource (lib "eagle-import") (part "74LVC3G17"))
    )
    (comp (ref "U208")
      (value "74LVC3G17")
      (footprint "eagle-import:TSSOP-8")
      (libsource (lib "eagle-import") (part "74LVC3G17"))
    )
    (comp (ref "C401")
      (value "100n")
      (footprint "eagle-import:0603_WAVE")
      (libsource (lib "eagle-import") (part "MLCC0603"))
    )
    (comp (ref "C402")
      (value "100n 25v")
      (footprint "eagle-import:0603_WAVE")
      (libsource (lib "eagle-import") (part "MLCC0603"))
    )
    (comp (ref "C403")
      (value "100n 25v")
      (footprint "eagle-import:0603_WAVE")
      (libsource (lib "eagle-import") (part "MLCC0603"))
    )
    (comp (ref "C404")
      (value "100n 25v")
      (footprint "eagle-import:0603_WAVE")
      (libsource (lib "eagle-import") (part "MLCC0603"))
    )
    (comp (ref "C405")
      (value "4u7")
      (footprint "eagle-import:0603_WAVE")
      (libsource (lib "eagle-import") (part "MLCC0603"))
    )
    (comp (ref "C406")
      (value "10u 25v")
      (footprint "eagle-import:0603_WAVE")
      (libsource (lib "eagle-import") (part "MLCC0603"))
    )
    (comp (ref "C407")
      (value "4u7")
      (footprint "eagle-import:0603_WAVE")
      (libsource (lib "eagle-import") (part "MLCC0603"))
    )
    (comp (ref "C408")
      (value "10u 25v")
      (footprint "eagle-import:0603_WAVE")
      (libsource (lib "eagle-import") (part "MLCC0603"))
    )
    (comp (ref "C409")
      (value "4u7")
      (footprint "eagle-import:0603_WAVE")
      (libsource (lib "eagle-import") (part "MLCC0603"))
    )
    (comp (ref "C410")
      (value "10u 25v")
      (footprint "eagle-import:0603_WAVE")
      (libsource (lib "eagle-import") (part "MLCC0603"))
    )
    (comp (ref "C411")
      (value "4u7")
      (footprint "eagle-import:0603_WAVE")
      (libsource (lib "eagle-import") (part "MLCC0603"))
    )
    (comp (ref "C412")
      (value "10u 25v")
      (footprint "eagle-import:0603_WAVE")
      (libsource (lib "eagle-import") (part "MLCC0603"))
    )
    (comp (ref "C413")
      (value "100n")
      (footprint "eagle-import:0603_WAVE")
      (libsource (lib "eagle-import") (part "MLCC0603"))
    )
    (comp (ref "C414")
      (value "100n")
      (footprint "eagle-import:0603_WAVE")
      (libsource (lib "eagle-import") (part "MLCC0603"))
    )
    (comp (ref "C415")
      (value "100n")
      (footprint "eagle-import:0603_WAVE")
      (libsource (lib "eagle-import") (part "MLCC0603"))
    )
    (comp (ref "C416")
      (value "100n")
      (footprint "eagle-import:0603_WAVE")
      (libsource (lib "eagle-import") (part "MLCC0603"))
    )
    (comp (ref "C417")
      (value "220n 25v")
      (footprint "eagle-import:0603_WAVE")
      (libsource (lib "eagle-import") (part "MLCC0603"))
    )
    (comp (ref "C418")
      (value "220n 25v")
      (footprint "eagle-import:0603_WAVE")
      (libsource (lib "eagle-import") (part "MLCC0603"))
    )
    (comp (ref "C419")
      (value "220n 25v")
      (footprint "eagle-import:0603_WAVE")
      (libsource (lib "eagle-import") (part "MLCC0603"))
    )
    (comp (ref "C420")
      (value "220n 25v")
      (footprint "eagle-import:0603_WAVE")
      (libsource (lib "eagle-import") (part "MLCC0603"))
    )
    (comp (ref "C421")
      (value "100n 25v")
      (footprint "eagle-import:0603_WAVE")
      (libsource (lib "eagle-import") (part "MLCC0603"))
    )
    (comp (ref "C422")
      (value "100n")
      (footprint "eagle-import:0603_WAVE")
      (libsource (lib "eagle-import") (part "MLCC0603"))
    )
    (comp (ref "C423")
      (value "100n")
      (footprint "eagle-import:0603_WAVE")
      (libsource (lib "eagle-import") (part "MLCC0603"))
    )
    (comp (ref "C424")
      (value "10u 25v")
      (footprint "eagle-import:0603_WAVE")
      (libsource (lib "eagle-import") (part "MLCC0603"))
    )
    (comp (ref "C425")
      (value "100p")
      (footprint "eagle-import:0603_WAVE")
      (libsource (lib "eagle-import") (part "MLCC0603"))
    )
    (comp (ref "C426")
      (value "100n")
      (footprint "eagle-import:0603_WAVE")
      (libsource (lib "eagle-import") (part "MLCC0603"))
    )
    (comp (ref "C427")
      (value "100n")
      (footprint "eagle-import:0603_WAVE")
      (libsource (lib "eagle-import") (part "MLCC0603"))
    )
    (comp (ref "C428")
      (value "100n")
      (footprint "eagle-import:0603_WAVE")
      (libsource (lib "eagle-import") (part "MLCC0603"))
    )
    (comp (ref "C429")
      (value "100n")
      (footprint "eagle-import:0603_WAVE")
      (libsource (lib "eagle-import") (part "MLCC0603"))
    )
    (comp (ref "C430")
      (value "100n")
      (footprint "eagle-import:0603_WAVE")
      (libsource (lib "eagle-import") (part "MLCC0603"))
    )
    (comp (ref "C431")
      (value "100n")
      (footprint "eagle-import:0603_WAVE")
      (libsource (lib "eagle-import") (part "MLCC0603"))
    )
    (comp (ref "C432")
      (value "100p")
      (footprint "eagle-import:0603_WAVE")
      (libsource (lib "eagle-import") (part "MLCC0603"))
    )
    (comp (ref "D401")
      (value "DSK24")
      (footprint "eagle-import:SOD-123")
      (libsource (lib "eagle-import") (part "DSK24"))
    )
    (comp (ref "D402")
      (value "DSK24")
      (footprint "eagle-import:SOD-123")
      (libsource (lib "eagle-import") (part "DSK24"))
    )
    (comp (ref "D403")
      (value "DSK24")
      (footprint "eagle-import:SOD-123")
      (libsource (lib "eagle-import") (part "DSK24"))
    )
    (comp (ref "D404")
      (value "DSK24")
      (footprint "eagle-import:SOD-123")
      (libsource (lib "eagle-import") (part "DSK24"))
    )
    (comp (ref "J401")
      (value "4P-6.35P")
      (footprint "eagle-import:4P-6.35P")
      (libsource (lib "eagle-import") (part "4P-6.35P"))
    )
    (comp (ref "J402")
      (value "SH-2")
      (footprint "eagle-import:SM02B-SSR-H-TB")
      (libsource (lib "eagle-import") (part "SH-2"))
    )
    (comp (ref "J403")
      (value "2P-6.35P")
      (footprint "eagle-import:2P-6.35P")
      (libsource (lib "eagle-import") (part "2P-6.35P"))
    )
    (comp (ref "P401")
      (value "POWPAD")
      (footprint "eagle-import:TH-HP")
      (libsource (lib "eagle-import") (part "POWPAD"))
    )
    (comp (ref "P402")
      (value "POWPAD")
      (footprint "eagle-import:TH-HP")
      (libsource (lib "eagle-import") (part "POWPAD"))
    )
    (comp (ref "P403")
      (value "POWPAD")
      (footprint "eagle-import:TH-HP")
      (libsource (lib "eagle-import") (part "POWPAD"))
    )
    (comp (ref "P404")
      (value "POWPAD")
      (footprint "eagle-import:TH-HP")
      (libsource (lib "eagle-import") (part "POWPAD"))
    )
    (comp (ref "P405")
      (value "POWPAD")
      (footprint "eagle-import:TH-HP")
      (libsource (lib "eagle-import") (part "POWPAD"))
    )
    (comp (ref "P406")
      (value "POWPAD")
      (footprint "eagle-import:TH-HP")
      (libsource (lib "eagle-import") (part "POWPAD"))
    )
    (comp (ref "Q401")
      (value "IRF7580")
      (footprint "eagle-import:DIRECTFET-ME")
      (libsource (lib "eagle-import") (part "IRF7580"))
    )
    (comp (ref "Q402")
      (value "IRF7580")
      (footprint "eagle-import:DIRECTFET-ME")
      (libsource (lib "eagle-import") (part "IRF7580"))
    )
    (comp (ref "Q403")
      (value "IRF7580")
      (footprint "eagle-import:DIRECTFET-ME")
      (libsource (lib "eagle-import") (part "IRF7580"))
    )
    (comp (ref "Q404")
      (value "IRF7580")
      (footprint "eagle-import:DIRECTFET-ME")
      (libsource (lib "eagle-import") (part "IRF7580"))
    )
    (comp (ref "Q405")
      (value "IRF7580")
      (footprint "eagle-import:DIRECTFET-ME")
      (libsource (lib "eagle-import") (part "IRF7580"))
    )
    (comp (ref "Q406")
      (value "IRF7580")
      (footprint "eagle-import:DIRECTFET-ME")
      (libsource (lib "eagle-import") (part "IRF7580"))
    )
    (comp (ref "Q407")
      (value "IRF7580")
      (footprint "eagle-import:DIRECTFET-ME")
      (libsource (lib "eagle-import") (part "IRF7580"))
    )
    (comp (ref "Q408")
      (value "IRF7580")
      (footprint "eagle-import:DIRECTFET-ME")
      (libsource (lib "eagle-import") (part "IRF7580"))
    )
    (comp (ref "Q409")
      (value "IRF7580")
      (footprint "eagle-import:DIRECTFET-ME")
      (libsource (lib "eagle-import") (part "IRF7580"))
    )
    (comp (ref "R401")
      (value "10k")
      (footprint "eagle-import:0603_WAVE")
      (libsource (lib "eagle-import") (part "RESISTOR0603"))
    )
    (comp (ref "R402")
      (value "10k")
      (footprint "eagle-import:0603_WAVE")
      (libsource (lib "eagle-import") (part "RESISTOR0603"))
    )
    (comp (ref "R403")
      (value "10k")
      (footprint "eagle-import:0603_WAVE")
      (libsource (lib "eagle-import") (part "RESISTOR0603"))
    )
    (comp (ref "R404")
      (value "10k")
      (footprint "eagle-import:0603_WAVE")
      (libsource (lib "eagle-import") (part "RESISTOR0603"))
    )
    (comp (ref "R405")
      (value "10k")
      (footprint "eagle-import:0603_WAVE")
      (libsource (lib "eagle-import") (part "RESISTOR0603"))
    )
    (comp (ref "R406")
      (value "10k")
      (footprint "eagle-import:0603_WAVE")
      (libsource (lib "eagle-import") (part "RESISTOR0603"))
    )
    (comp (ref "R407")
      (value "10k")
      (footprint "eagle-import:0603_WAVE")
      (libsource (lib "eagle-import") (part "RESISTOR0603"))
    )
    (comp (ref "R408")
      (value "10k")
      (footprint "eagle-import:0603_WAVE")
      (libsource (lib "eagle-import") (part "RESISTOR0603"))
    )
    (comp (ref "R409")
      (value "2.2")
      (footprint "eagle-import:0603_WAVE")
      (libsource (lib "eagle-import") (part "RESISTOR0603"))
    )
    (comp (ref "R410")
      (value "2.2")
      (footprint "eagle-import:0603_WAVE")
      (libsource (lib "eagle-import") (part "RESISTOR0603"))
    )
    (comp (ref "R411")
      (value "2.2")
      (footprint "eagle-import:0603_WAVE")
      (libsource (lib "eagle-import") (part "RESISTOR0603"))
    )
    (comp (ref "R412")
      (value "2.2")
      (footprint "eagle-import:0603_WAVE")
      (libsource (lib "eagle-import") (part "RESISTOR0603"))
    )
    (comp (ref "R413")
      (value "2.2")
      (footprint "eagle-import:0603_WAVE")
      (libsource (lib "eagle-import") (part "RESISTOR0603"))
    )
    (comp (ref "R414")
      (value "2.2")
      (footprint "eagle-import:0603_WAVE")
      (libsource (lib "eagle-import") (part "RESISTOR0603"))
    )
    (comp (ref "R415")
      (value "2.2")
      (footprint "eagle-import:0603_WAVE")
      (libsource (lib "eagle-import") (part "RESISTOR0603"))
    )
    (comp (ref "R416")
      (value "2.2")
      (footprint "eagle-import:0603_WAVE")
      (libsource (lib "eagle-import") (part "RESISTOR0603"))
    )
    (comp (ref "R417")
      (value "2.2")
      (footprint "eagle-import:0603_WAVE")
      (libsource (lib "eagle-import") (part "RESISTOR0603"))
    )
    (comp (ref "R418")
      (value "2.2")
      (footprint "eagle-import:0603_WAVE")
      (libsource (lib "eagle-import") (part "RESISTOR0603"))
    )
    (comp (ref "R419")
      (value "2.2")
      (footprint "eagle-import:0603_WAVE")
      (libsource (lib "eagle-import") (part "RESISTOR0603"))
    )
    (comp (ref "R420")
      (value "2.2")
      (footprint "eagle-import:0603_WAVE")
      (libsource (lib "eagle-import") (part "RESISTOR0603"))
    )
    (comp (ref "R421")
      (value "700u")
      (footprint "eagle-import:3920")
      (libsource (lib "eagle-import") (part "LRMAP3920"))
    )
    (comp (ref "R422")
      (value "700u")
      (footprint "eagle-import:3920")
      (libsource (lib "eagle-import") (part "LRMAP3920"))
    )
    (comp (ref "R423")
      (value "100")
      (footprint "eagle-import:0603_WAVE")
      (libsource (lib "eagle-import") (part "RESISTOR0603"))
    )
    (comp (ref "R424")
      (value "100")
      (footprint "eagle-import:0603_WAVE")
      (libsource (lib "eagle-import") (part "RESISTOR0603"))
    )
    (comp (ref "R425")
      (value "100")
      (footprint "eagle-import:0603_WAVE")
      (libsource (lib "eagle-import") (part "RESISTOR0603"))
    )
    (comp (ref "R426")
      (value "100")
      (footprint "eagle-import:0603_WAVE")
      (libsource (lib "eagle-import") (part "RESISTOR0603"))
    )
    (comp (ref "R427")
      (value "100k")
      (footprint "eagle-import:0603_WAVE")
      (libsource (lib "eagle-import") (part "NTC0603"))
    )
    (comp (ref "R428")
      (value "1k2")
      (footprint "eagle-import:0603_WAVE")
      (libsource (lib "eagle-import") (part "RESISTOR0603"))
    )
    (comp (ref "R429")
      (value "220")
      (footprint "eagle-import:0603_WAVE")
      (libsource (lib "eagle-import") (part "RESISTOR0603"))
    )
    (comp (ref "R430")
      (value "1k2")
      (footprint "eagle-import:0603_WAVE")
      (libsource (lib "eagle-import") (part "RESISTOR0603"))
    )
    (comp (ref "R431")
      (value "2.2")
      (footprint "eagle-import:0603_WAVE")
      (libsource (lib "eagle-import") (part "RESISTOR0603"))
    )
    (comp (ref "U401")
      (value "SI82397")
      (footprint "eagle-import:SOIC-16-WB")
      (libsource (lib "eagle-import") (part "SI82397"))
    )
    (comp (ref "U402")
      (value "SI82397")
      (footprint "eagle-import:SOIC-16-WB")
      (libsource (lib "eagle-import") (part "SI82397"))
    )
    (comp (ref "U403")
      (value "SI82397")
      (footprint "eagle-import:SOIC-16-WB")
      (libsource (lib "eagle-import") (part "SI82397"))
    )
    (comp (ref "U404")
      (value "SI82397")
      (footprint "eagle-import:SOIC-16-WB")
      (libsource (lib "eagle-import") (part "SI82397"))
    )
    (comp (ref "U405")
      (value "AD8418A")
      (footprint "eagle-import:MSOP-8")
      (libsource (lib "eagle-import") (part "AD8418A"))
    )
    (comp (ref "U406")
      (value "AD8418A")
      (footprint "eagle-import:MSOP-8")
      (libsource (lib "eagle-import") (part "AD8418A"))
    )
    (comp (ref "U407")
      (value "SI8261")
      (footprint "eagle-import:SOIC_8")
      (libsource (lib "eagle-import") (part "SI8261"))
    )
    (comp (ref "C301")
      (value "4u7")
      (footprint "eagle-import:0603_WAVE")
      (libsource (lib "eagle-import") (part "MLCC0603"))
    )
    (comp (ref "C302")
      (value "100u")
      (footprint "eagle-import:PANASONIC_D")
      (libsource (lib "eagle-import") (part "CAPACITOR_ELD"))
    )
    (comp (ref "C303")
      (value "330u")
      (footprint "eagle-import:PANASONIC_G")
      (libsource (lib "eagle-import") (part "CAPACITOR_ELG"))
    )
    (comp (ref "C304")
      (value "330u")
      (footprint "eagle-import:PANASONIC_G")
      (libsource (lib "eagle-import") (part "CAPACITOR_ELG"))
    )
    (comp (ref "C305")
      (value "4u7")
      (footprint "eagle-import:0603_WAVE")
      (libsource (lib "eagle-import") (part "MLCC0603"))
    )
    (comp (ref "C306")
      (value "330u")
      (footprint "eagle-import:PANASONIC_G")
      (libsource (lib "eagle-import") (part "CAPACITOR_ELG"))
    )
    (comp (ref "C307")
      (value "100u")
      (footprint "eagle-import:PANASONIC_D")
      (libsource (lib "eagle-import") (part "CAPACITOR_ELD"))
    )
    (comp (ref "C308")
      (value "330u")
      (footprint "eagle-import:PANASONIC_G")
      (libsource (lib "eagle-import") (part "CAPACITOR_ELG"))
    )
    (comp (ref "C309")
      (value "4u7")
      (footprint "eagle-import:0603_WAVE")
      (libsource (lib "eagle-import") (part "MLCC0603"))
    )
    (comp (ref "C310")
      (value "4u7")
      (footprint "eagle-import:0603_WAVE")
      (libsource (lib "eagle-import") (part "MLCC0603"))
    )
    (comp (ref "D301")
      (value "SK54L")
      (footprint "eagle-import:DO214AA")
      (libsource (lib "eagle-import") (part "SK54L"))
    )
    (comp (ref "D302")
      (value "LED0603")
      (footprint "eagle-import:CHIPLED_0603")
      (libsource (lib "eagle-import") (part "LED0603"))
    )
    (comp (ref "J301")
      (value "2P-6.35P")
      (footprint "eagle-import:2P-6.35P")
      (libsource (lib "eagle-import") (part "2P-6.35P"))
    )
    (comp (ref "J302")
      (value "2P-6.35P")
      (footprint "eagle-import:2P-6.35P")
      (libsource (lib "eagle-import") (part "2P-6.35P"))
    )
    (comp (ref "L301")
      (value "68uH")
      (footprint "eagle-import:CDRH104R")
      (libsource (lib "eagle-import") (part "INDUCTORCDRH104R"))
    )
    (comp (ref "P301")
      (value "POWPAD")
      (footprint "eagle-import:TH-HP")
      (libsource (lib "eagle-import") (part "POWPAD"))
    )
    (comp (ref "P302")
      (value "POWPAD")
      (footprint "eagle-import:TH-HP")
      (libsource (lib "eagle-import") (part "POWPAD"))
    )
    (comp (ref "R301")
      (value "10M")
      (footprint "eagle-import:0603_WAVE")
      (libsource (lib "eagle-import") (part "RESISTOR0603"))
    )
    (comp (ref "R302")
      (value "10k")
      (footprint "eagle-import:0603_WAVE")
      (libsource (lib "eagle-import") (part "RESISTOR0603"))
    )
    (comp (ref "R303")
      (value "4.2k")
      (footprint "eagle-import:0603_WAVE")
      (libsource (lib "eagle-import") (part "RESISTOR0603"))
    )
    (comp (ref "R304")
      (value "1.2k")
      (footprint "eagle-import:0603_WAVE")
      (libsource (lib "eagle-import") (part "RESISTOR0603"))
    )
    (comp (ref "R305")
      (value "2k")
      (footprint "eagle-import:0603_WAVE")
      (libsource (lib "eagle-import") (part "RESISTOR0603"))
    )
    (comp (ref "U301")
      (value "MIC4682")
      (footprint "eagle-import:SOIC8")
      (libsource (lib "eagle-import") (part "MIC4682"))
    )
    (comp (ref "U302")
      (value "MIC39101")
      (footprint "eagle-import:SOIC8")
      (libsource (lib "eagle-import") (part "MIC39101"))
    )
    (comp (ref "U303")
      (value "MIC39101")
      (footprint "eagle-import:SOIC8")
      (libsource (lib "eagle-import") (part "MIC39101"))
    )
  )
  (nets
    (net (code "1") (name "1.8V") (class "Default")
      (node (ref "C103") (pin "P$1") (pinfunction "P$1_P$1") (pintype "bidirectional"))
      (node (ref "C105") (pin "P$1") (pinfunction "P$1_P$1") (pintype "bidirectional"))
      (node (ref "C107") (pin "P$1") (pinfunction "P$1_P$1") (pintype "bidirectional"))
      (node (ref "U102") (pin "15") (pinfunction "VCC_CORE_15") (pintype "bidirectional"))
      (node (ref "U102") (pin "45") (pinfunction "VCC_CORE_45") (pintype "bidirectional"))
      (node (ref "U102") (pin "63") (pinfunction "VCC_CORE_63") (pintype "bidirectional"))
    )
    (net (code "2") (name "3.3V") (class "Default")
      (node (ref "C101") (pin "P$1") (pinfunction "P$1_P$1") (pintype "bidirectional"))
      (node (ref "C102") (pin "P$1") (pinfunction "P$1_P$1") (pintype "bidirectional"))
      (node (ref "C104") (pin "P$1") (pinfunction "P$1_P$1") (pintype "bidirectional"))
      (node (ref "C106") (pin "P$1") (pinfunction "P$1_P$1") (pintype "bidirectional"))
      (node (ref "C108") (pin "P$1") (pinfunction "P$1_P$1") (pintype "bidirectional"))
      (node (ref "C109") (pin "P$1") (pinfunction "P$1_P$1") (pintype "bidirectional"))
      (node (ref "C110") (pin "P$1") (pinfunction "P$1_P$1") (pintype "bidirectional"))
      (node (ref "C111") (pin "P$1") (pinfunction "P$1_P$1") (pintype "bidirectional"))
      (node (ref "C214") (pin "P$1") (pinfunction "P$1_P$1") (pintype "bidirectional"))
      (node (ref "C215") (pin "P$1") (pinfunction "P$1_P$1") (pintype "bidirectional"))
      (node (ref "C216") (pin "P$1") (pinfunction "P$1_P$1") (pintype "bidirectional"))
      (node (ref "C217") (pin "P$1") (pinfunction "P$1_P$1") (pintype "bidirectional"))
      (node (ref "C309") (pin "P$1") (pinfunction "P$1_P$1") (pintype "bidirectional"))
      (node (ref "C405") (pin "P$1") (pinfunction "P$1_P$1") (pintype "bidirectional"))
      (node (ref "C407") (pin "P$1") (pinfunction "P$1_P$1") (pintype "bidirectional"))
      (node (ref "C409") (pin "P$1") (pinfunction "P$1_P$1") (pintype "bidirectional"))
      (node (ref "C411") (pin "P$1") (pinfunction "P$1_P$1") (pintype "bidirectional"))
      (node (ref "C413") (pin "P$1") (pinfunction "P$1_P$1") (pintype "bidirectional"))
      (node (ref "C414") (pin "P$1") (pinfunction "P$1_P$1") (pintype "bidirectional"))
      (node (ref "C415") (pin "P$1") (pinfunction "P$1_P$1") (pintype "bidirectional"))
      (node (ref "C416") (pin "P$1") (pinfunction "P$1_P$1") (pintype "bidirectional"))
      (node (ref "C501") (pin "P$1") (pinfunction "P$1_P$1") (pintype "bidirectional"))
      (node (ref "C502") (pin "P$1") (pinfunction "P$1_P$1") (pintype "bidirectional"))
      (node (ref "D504") (pin "P$2") (pinfunction "2_P$2") (pintype "bidirectional"))
      (node (ref "D505") (pin "P$2") (pinfunction "2_P$2") (pintype "bidirectional"))
      (node (ref "D506") (pin "P$2") (pinfunction "2_P$2") (pintype "bidirectional"))
      (node (ref "J505") (pin "1") (pinfunction "S_1") (pintype "passive"))
      (node (ref "R101") (pin "P$2") (pinfunction "P$2_P$2") (pintype "bidirectional"))
      (node (ref "R102") (pin "P$1") (pinfunction "P$1_P$1") (pintype "bidirectional"))
      (node (ref "R501") (pin "P$1") (pinfunction "P$1_P$1") (pintype "bidirectional"))
      (node (ref "R502") (pin "P$2") (pinfunction "P$2_P$2") (pintype "bidirectional"))
      (node (ref "R503") (pin "P$2") (pinfunction "P$2_P$2") (pintype "bidirectional"))
      (node (ref "U101") (pin "6") (pinfunction "VDD_6") (pintype "bidirectional"))
      (node (ref "U102") (pin "13") (pinfunction "VCC_13") (pintype "bidirectional"))
      (node (ref "U102") (pin "2") (pinfunction "VCC_2") (pintype "bidirectional"))
      (node (ref "U102") (pin "43") (pinfunction "VCC_43") (pintype "bidirectional"))
      (node (ref "U102") (pin "52") (pinfunction "PLL_VCC_52") (pintype "bidirectional"))
      (node (ref "U102") (pin "61") (pinfunction "VCC_61") (pintype "bidirectional"))
      (node (ref "U102") (pin "72") (pinfunction "VCC_72") (pintype "bidirectional"))
      (node (ref "U205") (pin "8") (pinfunction "VCC_8") (pintype "bidirectional"))
      (node (ref "U206") (pin "8") (pinfunction "VCC_8") (pintype "bidirectional"))
      (node (ref "U207") (pin "8") (pinfunction "VCC_8") (pintype "bidirectional"))
      (node (ref "U208") (pin "8") (pinfunction "VCC_8") (pintype "bidirectional"))
      (node (ref "U302") (pin "3") (pinfunction "VOUT_3") (pintype "bidirectional"))
      (node (ref "U401") (pin "3") (pinfunction "VDDI_3") (pintype "bidirectional"))
      (node (ref "U401") (pin "8") (pinfunction "VDDI_8") (pintype "bidirectional"))
      (node (ref "U402") (pin "3") (pinfunction "VDDI_3") (pintype "bidirectional"))
      (node (ref "U402") (pin "8") (pinfunction "VDDI_8") (pintype "bidirectional"))
      (node (ref "U403") (pin "3") (pinfunction "VDDI_3") (pintype "bidirectional"))
      (node (ref "U403") (pin "8") (pinfunction "VDDI_8") (pintype "bidirectional"))
      (node (ref "U404") (pin "3") (pinfunction "VDDI_3") (pintype "bidirectional"))
      (node (ref "U404") (pin "8") (pinfunction "VDDI_8") (pintype "bidirectional"))
      (node (ref "U501") (pin "5") (pinfunction "VIO_5") (pintype "bidirectional"))
      (node (ref "U501") (pin "6") (pinfunction "VDD_6") (pintype "bidirectional"))
      (node (ref "U501") (pin "7") (pinfunction "VREGIN_7") (pintype "bidirectional"))
    )
    (net (code "3") (name "5V") (class "Default")
      (node (ref "C112") (pin "P$1") (pinfunction "P$1_P$1") (pintype "bidirectional"))
      (node (ref "C113") (pin "P$1") (pinfunction "P$1_P$1") (pintype "bidirectional"))
      (node (ref "C201") (pin "P$1") (pinfunction "P$1_P$1") (pintype "bidirectional"))
      (node (ref "C202") (pin "P$1") (pinfunction "P$1_P$1") (pintype "bidirectional"))
      (node (ref "C203") (pin "P$1") (pinfunction "P$1_P$1") (pintype "bidirectional"))
      (node (ref "C204") (pin "P$1") (pinfunction "P$1_P$1") (pintype "bidirectional"))
      (node (ref "C205") (pin "P$1") (pinfunction "P$1_P$1") (pintype "bidirectional"))
      (node (ref "C222") (pin "P$1") (pinfunction "P$1_P$1") (pintype "bidirectional"))
      (node (ref "C223") (pin "P$1") (pinfunction "P$1_P$1") (pintype "bidirectional"))
      (node (ref "C224") (pin "P$1") (pinfunction "P$1_P$1") (pintype "bidirectional"))
      (node (ref "C225") (pin "P$1") (pinfunction "P$1_P$1") (pintype "bidirectional"))
      (node (ref "C310") (pin "P$1") (pinfunction "P$1_P$1") (pintype "bidirectional"))
      (node (ref "C422") (pin "P$1") (pinfunction "P$1_P$1") (pintype "bidirectional"))
      (node (ref "C423") (pin "P$1") (pinfunction "P$1_P$1") (pintype "bidirectional"))
      (node (ref "D101") (pin "P$2") (pinfunction "2_P$2") (pintype "bidirectional"))
      (node (ref "D201") (pin "P$2") (pinfunction "2_P$2") (pintype "bidirectional"))
      (node (ref "D202") (pin "P$2") (pinfunction "2_P$2") (pintype "bidirectional"))
      (node (ref "D203") (pin "P$2") (pinfunction "2_P$2") (pintype "bidirectional"))
      (node (ref "J201") (pin "1") (pinfunction "S_1") (pintype "passive"))
      (node (ref "J202") (pin "1") (pinfunction "S_1") (pintype "passive"))
      (node (ref "J203") (pin "1") (pinfunction "S_1") (pintype "passive"))
      (node (ref "J204") (pin "1") (pinfunction "S_1") (pintype "passive"))
      (node (ref "J205") (pin "1") (pinfunction "S_1") (pintype "passive"))
      (node (ref "J402") (pin "1") (pinfunction "S_1") (pintype "passive"))
      (node (ref "R103") (pin "P$2") (pinfunction "P$2_P$2") (pintype "bidirectional"))
      (node (ref "R106") (pin "P$2") (pinfunction "P$2_P$2") (pintype "bidirectional"))
      (node (ref "R109") (pin "P$2") (pinfunction "P$2_P$2") (pintype "bidirectional"))
      (node (ref "R117") (pin "P$2") (pinfunction "P$2_P$2") (pintype "bidirectional"))
      (node (ref "R120") (pin "P$2") (pinfunction "P$2_P$2") (pintype "bidirectional"))
      (node (ref "R214") (pin "P$1") (pinfunction "P$1_P$1") (pintype "bidirectional"))
      (node (ref "R215") (pin "P$1") (pinfunction "P$1_P$1") (pintype "bidirectional"))
      (node (ref "R216") (pin "P$1") (pinfunction "P$1_P$1") (pintype "bidirectional"))
      (node (ref "R217") (pin "P$1") (pinfunction "P$1_P$1") (pintype "bidirectional"))
      (node (ref "R219") (pin "P$1") (pinfunction "P$1_P$1") (pintype "bidirectional"))
      (node (ref "R220") (pin "P$1") (pinfunction "P$1_P$1") (pintype "bidirectional"))
      (node (ref "R221") (pin "P$1") (pinfunction "P$1_P$1") (pintype "bidirectional"))
      (node (ref "R222") (pin "P$1") (pinfunction "P$1_P$1") (pintype "bidirectional"))
      (node (ref "R223") (pin "P$1") (pinfunction "P$1_P$1") (pintype "bidirectional"))
      (node (ref "R224") (pin "P$1") (pinfunction "P$1_P$1") (pintype "bidirectional"))
      (node (ref "R225") (pin "P$1") (pinfunction "P$1_P$1") (pintype "bidirectional"))
      (node (ref "R226") (pin "P$1") (pinfunction "P$1_P$1") (pintype "bidirectional"))
      (node (ref "R427") (pin "P$2") (pinfunction "P$2_P$2") (pintype "bidirectional"))
      (node (ref "U102") (pin "23") (pinfunction "V5_23") (pintype "bidirectional"))
      (node (ref "U201") (pin "5") (pinfunction "VCC_5") (pintype "bidirectional"))
      (node (ref "U202") (pin "5") (pinfunction "VCC_5") (pintype "bidirectional"))
      (node (ref "U203") (pin "5") (pinfunction "VCC_5") (pintype "bidirectional"))
      (node (ref "U204") (pin "5") (pinfunction "VCC_5") (pintype "bidirectional"))
      (node (ref "U303") (pin "3") (pinfunction "VOUT_3") (pintype "bidirectional"))
      (node (ref "U405") (pin "6") (pinfunction "P$1_6") (pintype "bidirectional"))
      (node (ref "U405") (pin "7") (pinfunction "P$1_7") (pintype "bidirectional"))
      (node (ref "U406") (pin "6") (pinfunction "P$1_6") (pintype "bidirectional"))
      (node (ref "U406") (pin "7") (pinfunction "P$1_7") (pintype "bidirectional"))
    )
    (net (code "4") (name "12V") (class "Default")
      (node (ref "C301") (pin "P$1") (pinfunction "P$1_P$1") (pintype "bidirectional"))
      (node (ref "C302") (pin "+") (pinfunction "AN_+") (pintype "bidirectional"))
      (node (ref "C401") (pin "P$1") (pinfunction "P$1_P$1") (pintype "bidirectional"))
      (node (ref "C402") (pin "P$1") (pinfunction "P$1_P$1") (pintype "bidirectional"))
      (node (ref "C403") (pin "P$1") (pinfunction "P$1_P$1") (pintype "bidirectional"))
      (node (ref "C404") (pin "P$1") (pinfunction "P$1_P$1") (pintype "bidirectional"))
      (node (ref "C406") (pin "P$1") (pinfunction "P$1_P$1") (pintype "bidirectional"))
      (node (ref "C408") (pin "P$1") (pinfunction "P$1_P$1") (pintype "bidirectional"))
      (node (ref "C410") (pin "P$1") (pinfunction "P$1_P$1") (pintype "bidirectional"))
      (node (ref "C412") (pin "P$1") (pinfunction "P$1_P$1") (pintype "bidirectional"))
      (node (ref "C421") (pin "P$1") (pinfunction "P$1_P$1") (pintype "bidirectional"))
      (node (ref "C424") (pin "P$1") (pinfunction "P$1_P$1") (pintype "bidirectional"))
      (node (ref "J301") (pin "2") (pinfunction "S_2") (pintype "passive"))
      (node (ref "R301") (pin "P$2") (pinfunction "P$2_P$2") (pintype "bidirectional"))
      (node (ref "R409") (pin "P$1") (pinfunction "P$1_P$1") (pintype "bidirectional"))
      (node (ref "R410") (pin "P$1") (pinfunction "P$1_P$1") (pintype "bidirectional"))
      (node (ref "R411") (pin "P$1") (pinfunction "P$1_P$1") (pintype "bidirectional"))
      (node (ref "R412") (pin "P$1") (pinfunction "P$1_P$1") (pintype "bidirectional"))
      (node (ref "U301") (pin "5") (pinfunction "IN_5") (pintype "bidirectional"))
      (node (ref "U401") (pin "11") (pinfunction "VDDB_11") (pintype "bidirectional"))
      (node (ref "U402") (pin "11") (pinfunction "VDDB_11") (pintype "bidirectional"))
      (node (ref "U403") (pin "11") (pinfunction "VDDB_11") (pintype "bidirectional"))
      (node (ref "U404") (pin "11") (pinfunction "VDDB_11") (pintype "bidirectional"))
      (node (ref "U407") (pin "8") (pinfunction "VDD_8") (pintype "bidirectional"))
    )
    (net (code "5") (name "ADC_I0_U_PF") (class "Default")
      (node (ref "R113") (pin "P$2") (pinfunction "P$2_P$2") (pintype "bidirectional"))
      (node (ref "U405") (pin "5") (pinfunction "O_5") (pintype "bidirectional"))
    )
    (net (code "6") (name "ADC_I1_V_PF") (class "Default")
      (node (ref "R115") (pin "P$2") (pinfunction "P$2_P$2") (pintype "bidirectional"))
      (node (ref "U406") (pin "5") (pinfunction "O_5") (pintype "bidirectional"))
    )
    (net (code "7") (name "ADC_T_MOSFETS") (class "Default")
      (node (ref "C425") (pin "P$1") (pinfunction "P$1_P$1") (pintype "bidirectional"))
      (node (ref "R111") (pin "P$2") (pinfunction "P$2_P$2") (pintype "bidirectional"))
      (node (ref "R427") (pin "P$1") (pinfunction "P$1_P$1") (pintype "bidirectional"))
      (node (ref "R428") (pin "P$2") (pinfunction "P$2_P$2") (pintype "bidirectional"))
    )
    (net (code "8") (name "ADC_T_MOTOR") (class "Default")
      (node (ref "C432") (pin "P$1") (pinfunction "P$1_P$1") (pintype "bidirectional"))
      (node (ref "J402") (pin "2") (pinfunction "S_2") (pintype "passive"))
      (node (ref "R112") (pin "P$1") (pinfunction "P$1_P$1") (pintype "bidirectional"))
      (node (ref "R430") (pin "P$2") (pinfunction "P$2_P$2") (pintype "bidirectional"))
    )
    (net (code "9") (name "AENC_UX_P") (class "Default")
      (node (ref "C226") (pin "P$1") (pinfunction "P$1_P$1") (pintype "bidirectional"))
      (node (ref "D201") (pin "P$3") (pinfunction "3_P$3") (pintype "bidirectional"))
      (node (ref "R213") (pin "P$2") (pinfunction "P$2_P$2") (pintype "bidirectional"))
      (node (ref "U102") (pin "25") (pinfunction "AENC_UX_POS_25") (pintype "bidirectional"))
    )
    (net (code "10") (name "AENC_VN_P") (class "Default")
      (node (ref "C227") (pin "P$1") (pinfunction "P$1_P$1") (pintype "bidirectional"))
      (node (ref "D202") (pin "P$3") (pinfunction "3_P$3") (pintype "bidirectional"))
      (node (ref "R218") (pin "P$2") (pinfunction "P$2_P$2") (pintype "bidirectional"))
      (node (ref "U102") (pin "27") (pinfunction "AENC_VN_POS_27") (pintype "bidirectional"))
    )
    (net (code "11") (name "AENC_WY_P") (class "Default")
      (node (ref "C228") (pin "P$1") (pinfunction "P$1_P$1") (pintype "bidirectional"))
      (node (ref "D203") (pin "P$3") (pinfunction "3_P$3") (pintype "bidirectional"))
      (node (ref "R227") (pin "P$2") (pinfunction "P$2_P$2") (pintype "bidirectional"))
      (node (ref "U102") (pin "29") (pinfunction "AENC_WY_POS_29") (pintype "bidirectional"))
    )
    (net (code "12") (name "BRAKE") (class "Default")
      (node (ref "R429") (pin "P$2") (pinfunction "P$2_P$2") (pintype "bidirectional"))
      (node (ref "U102") (pin "31") (pinfunction "BRAKE_31") (pintype "bidirectional"))
    )
    (net (code "13") (name "CP2102_RX") (class "Default")
      (node (ref "J502") (pin "2") (pinfunction "S_2") (pintype "passive"))
      (node (ref "JP505") (pin "2") (pinfunction "2_2") (pintype "passive"))
      (node (ref "U102") (pin "11") (pinfunction "TXD_SYNCO_11") (pintype "bidirectional"))
    )
    (net (code "14") (name "CP2102_TX") (class "Default")
      (node (ref "J502") (pin "1") (pinfunction "S_1") (pintype "passive"))
      (node (ref "JP506") (pin "2") (pinfunction "2_2") (pintype "passive"))
      (node (ref "U102") (pin "10") (pinfunction "RXD_SYNCI_10") (pintype "bidirectional"))
    )
    (net (code "15") (name "D+") (class "Default")
      (node (ref "D503") (pin "3") (pinfunction "3_3") (pintype "bidirectional"))
      (node (ref "J503") (pin "D+") (pinfunction "D+_D+") (pintype "bidirectional"))
      (node (ref "U501") (pin "3") (pinfunction "D+_3") (pintype "bidirectional"))
    )
    (net (code "16") (name "D-") (class "Default")
      (node (ref "D503") (pin "2") (pinfunction "2_2") (pintype "bidirectional"))
      (node (ref "J503") (pin "D-") (pinfunction "D-_D-") (pintype "bidirectional"))
      (node (ref "U501") (pin "4") (pinfunction "D-_4") (pintype "bidirectional"))
    )
    (net (code "17") (name "DBG_SPI_MISO") (class "Default")
      (node (ref "J505") (pin "9") (pinfunction "S_9") (pintype "passive"))
      (node (ref "U102") (pin "4") (pinfunction "GPIO6_4") (pintype "bidirectional"))
    )
    (net (code "18") (name "DBG_SPI_MOSI") (class "Default")
      (node (ref "J505") (pin "7") (pinfunction "S_7") (pintype "passive"))
      (node (ref "U102") (pin "1") (pinfunction "GPIO5_1") (pintype "bidirectional"))
    )
    (net (code "19") (name "DBG_SPI_NSCS") (class "Default")
      (node (ref "J505") (pin "3") (pinfunction "S_3") (pintype "passive"))
      (node (ref "U102") (pin "75") (pinfunction "GPIO3_75") (pintype "bidirectional"))
    )
    (net (code "20") (name "DBG_SPI_SCK") (class "Default")
      (node (ref "J505") (pin "5") (pinfunction "S_5") (pintype "passive"))
      (node (ref "U102") (pin "76") (pinfunction "GPIO4_76") (pintype "bidirectional"))
    )
    (net (code "21") (name "DBG_SPI_TRG") (class "Default")
      (node (ref "J505") (pin "4") (pinfunction "S_4") (pintype "passive"))
      (node (ref "U102") (pin "5") (pinfunction "GPIO7_5") (pintype "bidirectional"))
    )
    (net (code "22") (name "DCBUS") (class "Default")
      (node (ref "C303") (pin "+") (pinfunction "AN_+") (pintype "bidirectional"))
      (node (ref "C304") (pin "+") (pinfunction "AN_+") (pintype "bidirectional"))
      (node (ref "C306") (pin "+") (pinfunction "AN_+") (pintype "bidirectional"))
      (node (ref "C308") (pin "+") (pinfunction "AN_+") (pintype "bidirectional"))
      (node (ref "J302") (pin "1") (pinfunction "S_1") (pintype "passive"))
      (node (ref "J403") (pin "1") (pinfunction "S_1") (pintype "passive"))
      (node (ref "P301") (pin "H1") (pinfunction "S_H1") (pintype "passive"))
      (node (ref "P301") (pin "H10") (pinfunction "S_H10") (pintype "passive"))
      (node (ref "P301") (pin "H11") (pinfunction "S_H11") (pintype "passive"))
      (node (ref "P301") (pin "H12") (pinfunction "S_H12") (pintype "passive"))
      (node (ref "P301") (pin "H2") (pinfunction "S_H2") (pintype "passive"))
      (node (ref "P301") (pin "H3") (pinfunction "S_H3") (pintype "passive"))
      (node (ref "P301") (pin "H4") (pinfunction "S_H4") (pintype "passive"))
      (node (ref "P301") (pin "H5") (pinfunction "S_H5") (pintype "passive"))
      (node (ref "P301") (pin "H6") (pinfunction "S_H6") (pintype "passive"))
      (node (ref "P301") (pin "H7") (pinfunction "S_H7") (pintype "passive"))
      (node (ref "P301") (pin "H8") (pinfunction "S_H8") (pintype "passive"))
      (node (ref "P301") (pin "H9") (pinfunction "S_H9") (pintype "passive"))
      (node (ref "P301") (pin "PAD") (pinfunction "S_PAD") (pintype "passive"))
      (node (ref "P405") (pin "H1") (pinfunction "S_H1") (pintype "passive"))
      (node (ref "P405") (pin "H10") (pinfunction "S_H10") (pintype "passive"))
      (node (ref "P405") (pin "H11") (pinfunction "S_H11") (pintype "passive"))
      (node (ref "P405") (pin "H12") (pinfunction "S_H12") (pintype "passive"))
      (node (ref "P405") (pin "H2") (pinfunction "S_H2") (pintype "passive"))
      (node (ref "P405") (pin "H3") (pinfunction "S_H3") (pintype "passive"))
      (node (ref "P405") (pin "H4") (pinfunction "S_H4") (pintype "passive"))
      (node (ref "P405") (pin "H5") (pinfunction "S_H5") (pintype "passive"))
      (node (ref "P405") (pin "H6") (pinfunction "S_H6") (pintype "passive"))
      (node (ref "P405") (pin "H7") (pinfunction "S_H7") (pintype "passive"))
      (node (ref "P405") (pin "H8") (pinfunction "S_H8") (pintype "passive"))
      (node (ref "P405") (pin "H9") (pinfunction "S_H9") (pintype "passive"))
      (node (ref "P405") (pin "PAD") (pinfunction "S_PAD") (pintype "passive"))
      (node (ref "Q401") (pin "D1") (pinfunction "D1_D1") (pintype "bidirectional"))
      (node (ref "Q401") (pin "D2") (pinfunction "D1_D2") (pintype "bidirectional"))
      (node (ref "Q401") (pin "D3") (pinfunction "D1_D3") (pintype "bidirectional"))
      (node (ref "Q401") (pin "D4") (pinfunction "D1_D4") (pintype "bidirectional"))
      (node (ref "Q402") (pin "D1") (pinfunction "D1_D1") (pintype "bidirectional"))
      (node (ref "Q402") (pin "D2") (pinfunction "D1_D2") (pintype "bidirectional"))
      (node (ref "Q402") (pin "D3") (pinfunction "D1_D3") (pintype "bidirectional"))
      (node (ref "Q402") (pin "D4") (pinfunction "D1_D4") (pintype "bidirectional"))
      (node (ref "Q403") (pin "D1") (pinfunction "D1_D1") (pintype "bidirectional"))
      (node (ref "Q403") (pin "D2") (pinfunction "D1_D2") (pintype "bidirectional"))
      (node (ref "Q403") (pin "D3") (pinfunction "D1_D3") (pintype "bidirectional"))
      (node (ref "Q403") (pin "D4") (pinfunction "D1_D4") (pintype "bidirectional"))
      (node (ref "Q404") (pin "D1") (pinfunction "D1_D1") (pintype "bidirectional"))
      (node (ref "Q404") (pin "D2") (pinfunction "D1_D2") (pintype "bidirectional"))
      (node (ref "Q404") (pin "D3") (pinfunction "D1_D3") (pintype "bidirectional"))
      (node (ref "Q404") (pin "D4") (pinfunction "D1_D4") (pintype "bidirectional"))
      (node (ref "R119") (pin "P$2") (pinfunction "P$2_P$2") (pintype "bidirectional"))
    )
    (net (code "23") (name "DIR") (class "Default")
      (node (ref "D505") (pin "P$3") (pinfunction "3_P$3") (pintype "bidirectional"))
      (node (ref "R508") (pin "P$2") (pinfunction "P$2_P$2") (pintype "bidirectional"))
      (node (ref "R511") (pin "P$2") (pinfunction "P$2_P$2") (pintype "bidirectional"))
      (node (ref "U102") (pin "56") (pinfunction "DIR_56") (pintype "bidirectional"))
    )
    (net (code "24") (name "ENC2_A") (class "Default")
      (node (ref "U102") (pin "64") (pinfunction "ENC2_A_64") (pintype "bidirectional"))
      (node (ref "U206") (pin "7") (pinfunction "Y_7") (pintype "output"))
    )
    (net (code "25") (name "ENC2_B") (class "Default")
      (node (ref "U102") (pin "65") (pinfunction "ENC2_B_65") (pintype "bidirectional"))
      (node (ref "U206") (pin "5") (pinfunction "Y_5") (pintype "output"))
    )
    (net (code "26") (name "ENC2_N") (class "Default")
      (node (ref "U102") (pin "66") (pinfunction "ENC2_N_66") (pintype "bidirectional"))
      (node (ref "U206") (pin "2") (pinfunction "Y_2") (pintype "output"))
    )
    (net (code "27") (name "ENC_A") (class "Default")
      (node (ref "U102") (pin "35") (pinfunction "ENC_A_35") (pintype "bidirectional"))
      (node (ref "U205") (pin "7") (pinfunction "Y_7") (pintype "output"))
    )
    (net (code "28") (name "ENC_B") (class "Default")
      (node (ref "U102") (pin "34") (pinfunction "ENC_B_34") (pintype "bidirectional"))
      (node (ref "U205") (pin "5") (pinfunction "Y_5") (pintype "output"))
    )
    (net (code "29") (name "ENC_N") (class "Default")
      (node (ref "U102") (pin "33") (pinfunction "ENC_N_33") (pintype "bidirectional"))
      (node (ref "U205") (pin "2") (pinfunction "Y_2") (pintype "output"))
    )
    (net (code "30") (name "ENO") (class "Default")
      (node (ref "R114") (pin "P$1") (pinfunction "P$1_P$1") (pintype "bidirectional"))
      (node (ref "U102") (pin "32") (pinfunction "ENO_32") (pintype "bidirectional"))
      (node (ref "U401") (pin "5") (pinfunction "EN_5") (pintype "bidirectional"))
      (node (ref "U402") (pin "5") (pinfunction "EN_5") (pintype "bidirectional"))
      (node (ref "U403") (pin "5") (pinfunction "EN_5") (pintype "bidirectional"))
      (node (ref "U404") (pin "5") (pinfunction "EN_5") (pintype "bidirectional"))
    )
    (net (code "31") (name "GND") (class "Default")
      (node (ref "C101") (pin "P$2") (pinfunction "P$2_P$2") (pintype "bidirectional"))
      (node (ref "C102") (pin "P$2") (pinfunction "P$2_P$2") (pintype "bidirectional"))
      (node (ref "C103") (pin "P$2") (pinfunction "P$2_P$2") (pintype "bidirectional"))
      (node (ref "C104") (pin "P$2") (pinfunction "P$2_P$2") (pintype "bidirectional"))
      (node (ref "C105") (pin "P$2") (pinfunction "P$2_P$2") (pintype "bidirectional"))
      (node (ref "C106") (pin "P$2") (pinfunction "P$2_P$2") (pintype "bidirectional"))
      (node (ref "C107") (pin "P$2") (pinfunction "P$2_P$2") (pintype "bidirectional"))
      (node (ref "C108") (pin "P$2") (pinfunction "P$2_P$2") (pintype "bidirectional"))
      (node (ref "C109") (pin "P$2") (pinfunction "P$2_P$2") (pintype "bidirectional"))
      (node (ref "C110") (pin "P$2") (pinfunction "P$2_P$2") (pintype "bidirectional"))
      (node (ref "C111") (pin "P$2") (pinfunction "P$2_P$2") (pintype "bidirectional"))
      (node (ref "C112") (pin "P$2") (pinfunction "P$2_P$2") (pintype "bidirectional"))
      (node (ref "C113") (pin "P$2") (pinfunction "P$2_P$2") (pintype "bidirectional"))
      (node (ref "C114") (pin "P$2") (pinfunction "P$2_P$2") (pintype "bidirectional"))
      (node (ref "C115") (pin "P$2") (pinfunction "P$2_P$2") (pintype "bidirectional"))
      (node (ref "C116") (pin "P$2") (pinfunction "P$2_P$2") (pintype "bidirectional"))
      (node (ref "C117") (pin "P$2") (pinfunction "P$2_P$2") (pintype "bidirectional"))
      (node (ref "C118") (pin "P$2") (pinfunction "P$2_P$2") (pintype "bidirectional"))
      (node (ref "C201") (pin "P$2") (pinfunction "P$2_P$2") (pintype "bidirectional"))
      (node (ref "C202") (pin "P$2") (pinfunction "P$2_P$2") (pintype "bidirectional"))
      (node (ref "C203") (pin "P$2") (pinfunction "P$2_P$2") (pintype "bidirectional"))
      (node (ref "C204") (pin "P$2") (pinfunction "P$2_P$2") (pintype "bidirectional"))
      (node (ref "C205") (pin "P$2") (pinfunction "P$2_P$2") (pintype "bidirectional"))
      (node (ref "C206") (pin "P$2") (pinfunction "P$2_P$2") (pintype "bidirectional"))
      (node (ref "C207") (pin "P$2") (pinfunction "P$2_P$2") (pintype "bidirectional"))
      (node (ref "C208") (pin "P$2") (pinfunction "P$2_P$2") (pintype "bidirectional"))
      (node (ref "C209") (pin "P$2") (pinfunction "P$2_P$2") (pintype "bidirectional"))
      (node (ref "C210") (pin "P$2") (pinfunction "P$2_P$2") (pintype "bidirectional"))
      (node (ref "C211") (pin "P$2") (pinfunction "P$2_P$2") (pintype "bidirectional"))
      (node (ref "C212") (pin "P$2") (pinfunction "P$2_P$2") (pintype "bidirectional"))
      (node (ref "C213") (pin "P$2") (pinfunction "P$2_P$2") (pintype "bidirectional"))
      (node (ref "C214") (pin "P$2") (pinfunction "P$2_P$2") (pintype "bidirectional"))
      (node (ref "C215") (pin "P$2") (pinfunction "P$2_P$2") (pintype "bidirectional"))
      (node (ref "C216") (pin "P$2") (pinfunction "P$2_P$2") (pintype "bidirectional"))
      (node (ref "C217") (pin "P$2") (pinfunction "P$2_P$2") (pintype "bidirectional"))
      (node (ref "C218") (pin "P$2") (pinfunction "P$2_P$2") (pintype "bidirectional"))
      (node (ref "C219") (pin "P$2") (pinfunction "P$2_P$2") (pintype "bidirectional"))
      (node (ref "C220") (pin "P$2") (pinfunction "P$2_P$2") (pintype "bidirectional"))
      (node (ref "C221") (pin "P$2") (pinfunction "P$2_P$2") (pintype "bidirectional"))
      (node (ref "C222") (pin "P$2") (pinfunction "P$2_P$2") (pintype "bidirectional"))
      (node (ref "C223") (pin "P$2") (pinfunction "P$2_P$2") (pintype "bidirectional"))
      (node (ref "C224") (pin "P$2") (pinfunction "P$2_P$2") (pintype "bidirectional"))
      (node (ref "C225") (pin "P$2") (pinfunction "P$2_P$2") (pintype "bidirectional"))
      (node (ref "C226") (pin "P$2") (pinfunction "P$2_P$2") (pintype "bidirectional"))
      (node (ref "C227") (pin "P$2") (pinfunction "P$2_P$2") (pintype "bidirectional"))
      (node (ref "C228") (pin "P$2") (pinfunction "P$2_P$2") (pintype "bidirectional"))
      (node (ref "C301") (pin "P$2") (pinfunction "P$2_P$2") (pintype "bidirectional"))
      (node (ref "C302") (pin "-") (pinfunction "CA_-") (pintype "bidirectional"))
      (node (ref "C303") (pin "-") (pinfunction "CA_-") (pintype "bidirectional"))
      (node (ref "C304") (pin "-") (pinfunction "CA_-") (pintype "bidirectional"))
      (node (ref "C305") (pin "P$2") (pinfunction "P$2_P$2") (pintype "bidirectional"))
      (node (ref "C306") (pin "-") (pinfunction "CA_-") (pintype "bidirectional"))
      (node (ref "C307") (pin "-") (pinfunction "CA_-") (pintype "bidirectional"))
      (node (ref "C308") (pin "-") (pinfunction "CA_-") (pintype "bidirectional"))
      (node (ref "C309") (pin "P$2") (pinfunction "P$2_P$2") (pintype "bidirectional"))
      (node (ref "C310") (pin "P$2") (pinfunction "P$2_P$2") (pintype "bidirectional"))
      (node (ref "C401") (pin "P$2") (pinfunction "P$2_P$2") (pintype "bidirectional"))
      (node (ref "C402") (pin "P$2") (pinfunction "P$2_P$2") (pintype "bidirectional"))
      (node (ref "C403") (pin "P$2") (pinfunction "P$2_P$2") (pintype "bidirectional"))
      (node (ref "C404") (pin "P$2") (pinfunction "P$2_P$2") (pintype "bidirectional"))
      (node (ref "C405") (pin "P$2") (pinfunction "P$2_P$2") (pintype "bidirectional"))
      (node (ref "C406") (pin "P$2") (pinfunction "P$2_P$2") (pintype "bidirectional"))
      (node (ref "C407") (pin "P$2") (pinfunction "P$2_P$2") (pintype "bidirectional"))
      (node (ref "C408") (pin "P$2") (pinfunction "P$2_P$2") (pintype "bidirectional"))
      (node (ref "C409") (pin "P$2") (pinfunction "P$2_P$2") (pintype "bidirectional"))
      (node (ref "C410") (pin "P$2") (pinfunction "P$2_P$2") (pintype "bidirectional"))
      (node (ref "C411") (pin "P$2") (pinfunction "P$2_P$2") (pintype "bidirectional"))
      (node (ref "C412") (pin "P$2") (pinfunction "P$2_P$2") (pintype "bidirectional"))
      (node (ref "C413") (pin "P$2") (pinfunction "P$2_P$2") (pintype "bidirectional"))
      (node (ref "C414") (pin "P$2") (pinfunction "P$2_P$2") (pintype "bidirectional"))
      (node (ref "C415") (pin "P$2") (pinfunction "P$2_P$2") (pintype "bidirectional"))
      (node (ref "C416") (pin "P$2") (pinfunction "P$2_P$2") (pintype "bidirectional"))
      (node (ref "C421") (pin "P$2") (pinfunction "P$2_P$2") (pintype "bidirectional"))
      (node (ref "C422") (pin "P$2") (pinfunction "P$2_P$2") (pintype "bidirectional"))
      (node (ref "C423") (pin "P$2") (pinfunction "P$2_P$2") (pintype "bidirectional"))
      (node (ref "C424") (pin "P$2") (pinfunction "P$2_P$2") (pintype "bidirectional"))
      (node (ref "C425") (pin "P$2") (pinfunction "P$2_P$2") (pintype "bidirectional"))
      (node (ref "C426") (pin "P$1") (pinfunction "P$1_P$1") (pintype "bidirectional"))
      (node (ref "C428") (pin "P$2") (pinfunction "P$2_P$2") (pintype "bidirectional"))
      (node (ref "C429") (pin "P$1") (pinfunction "P$1_P$1") (pintype "bidirectional"))
      (node (ref "C431") (pin "P$2") (pinfunction "P$2_P$2") (pintype "bidirectional"))
      (node (ref "C432") (pin "P$2") (pinfunction "P$2_P$2") (pintype "bidirectional"))
      (node (ref "C501") (pin "P$2") (pinfunction "P$2_P$2") (pintype "bidirectional"))
      (node (ref "C502") (pin "P$2") (pinfunction "P$2_P$2") (pintype "bidirectional"))
      (node (ref "C503") (pin "P$2") (pinfunction "P$2_P$2") (pintype "bidirectional"))
      (node (ref "D101") (pin "P$1") (pinfunction "1_P$1") (pintype "bidirectional"))
      (node (ref "D201") (pin "P$1") (pinfunction "1_P$1") (pintype "bidirectional"))
      (node (ref "D202") (pin "P$1") (pinfunction "1_P$1") (pintype "bidirectional"))
      (node (ref "D203") (pin "P$1") (pinfunction "1_P$1") (pintype "bidirectional"))
      (node (ref "D301") (pin "A") (pinfunction "A_A") (pintype "bidirectional"))
      (node (ref "D302") (pin "C") (pinfunction "CA_C") (pintype "bidirectional"))
      (node (ref "D503") (pin "1") (pinfunction "1_1") (pintype "bidirectional"))
      (node (ref "D504") (pin "P$1") (pinfunction "1_P$1") (pintype "bidirectional"))
      (node (ref "D505") (pin "P$1") (pinfunction "1_P$1") (pintype "bidirectional"))
      (node (ref "D506") (pin "P$1") (pinfunction "1_P$1") (pintype "bidirectional"))
      (node (ref "J201") (pin "5") (pinfunction "S_5") (pintype "passive"))
      (node (ref "J201") (pin "FIT@1") (pinfunction "S_FIT@1") (pintype "passive"))
      (node (ref "J201") (pin "FIT@2") (pinfunction "S_FIT@2") (pintype "passive"))
      (node (ref "J202") (pin "5") (pinfunction "S_5") (pintype "passive"))
      (node (ref "J202") (pin "FIT@1") (pinfunction "S_FIT@1") (pintype "passive"))
      (node (ref "J202") (pin "FIT@2") (pinfunction "S_FIT@2") (pintype "passive"))
      (node (ref "J203") (pin "5") (pinfunction "S_5") (pintype "passive"))
      (node (ref "J203") (pin "FIT@1") (pinfunction "S_FIT@1") (pintype "passive"))
      (node (ref "J203") (pin "FIT@2") (pinfunction "S_FIT@2") (pintype "passive"))
      (node (ref "J204") (pin "5") (pinfunction "S_5") (pintype "passive"))
      (node (ref "J204") (pin "FIT@1") (pinfunction "S_FIT@1") (pintype "passive"))
      (node (ref "J204") (pin "FIT@2") (pinfunction "S_FIT@2") (pintype "passive"))
      (node (ref "J205") (pin "5") (pinfunction "S_5") (pintype "passive"))
      (node (ref "J205") (pin "FIT@1") (pinfunction "S_FIT@1") (pintype "passive"))
      (node (ref "J205") (pin "FIT@2") (pinfunction "S_FIT@2") (pintype "passive"))
      (node (ref "J301") (pin "1") (pinfunction "S_1") (pintype "passive"))
      (node (ref "J302") (pin "2") (pinfunction "S_2") (pintype "passive"))
      (node (ref "J402") (pin "FIT@1") (pinfunction "S_FIT@1") (pintype "passive"))
      (node (ref "J402") (pin "FIT@2") (pinfunction "S_FIT@2") (pintype "passive"))
      (node (ref "J501") (pin "6") (pinfunction "S_6") (pintype "passive"))
      (node (ref "J501") (pin "FIT@1") (pinfunction "S_FIT@1") (pintype "passive"))
      (node (ref "J501") (pin "FIT@2") (pinfunction "S_FIT@2") (pintype "passive"))
      (node (ref "J502") (pin "3") (pinfunction "S_3") (pintype "passive"))
      (node (ref "J502") (pin "FIT@1") (pinfunction "S_FIT@1") (pintype "passive"))
      (node (ref "J502") (pin "FIT@2") (pinfunction "S_FIT@2") (pintype "passive"))
      (node (ref "J503") (pin "GND") (pinfunction "GND_GND") (pintype "bidirectional"))
      (node (ref "J503") (pin "GND@1") (pinfunction "CASE_GND@1") (pintype "bidirectional"))
      (node (ref "J503") (pin "GND@2") (pinfunction "CASE_GND@2") (pintype "bidirectional"))
      (node (ref "J503") (pin "GND@3") (pinfunction "CASE_GND@3") (pintype "bidirectional"))
      (node (ref "J503") (pin "GND@4") (pinfunction "CASE_GND@4") (pintype "bidirectional"))
      (node (ref "J504") (pin "2") (pinfunction "S_2") (pintype "passive"))
      (node (ref "J504") (pin "FIT@1") (pinfunction "S_FIT@1") (pintype "passive"))
      (node (ref "J504") (pin "FIT@2") (pinfunction "S_FIT@2") (pintype "passive"))
      (node (ref "J505") (pin "10") (pinfunction "S_10") (pintype "passive"))
      (node (ref "J505") (pin "6") (pinfunction "S_6") (pintype "passive"))
      (node (ref "J505") (pin "8") (pinfunction "S_8") (pintype "passive"))
      (node (ref "J505") (pin "TAB1") (pinfunction "S_TAB1") (pintype "passive"))
      (node (ref "J505") (pin "TAB2") (pinfunction "S_TAB2") (pintype "passive"))
      (node (ref "J506") (pin "3") (pinfunction "S_3") (pintype "passive"))
      (node (ref "J506") (pin "FIT@1") (pinfunction "S_FIT@1") (pintype "passive"))
      (node (ref "J506") (pin "FIT@2") (pinfunction "S_FIT@2") (pintype "passive"))
      (node (ref "P302") (pin "H1") (pinfunction "S_H1") (pintype "passive"))
      (node (ref "P302") (pin "H10") (pinfunction "S_H10") (pintype "passive"))
      (node (ref "P302") (pin "H11") (pinfunction "S_H11") (pintype "passive"))
      (node (ref "P302") (pin "H12") (pinfunction "S_H12") (pintype "passive"))
      (node (ref "P302") (pin "H2") (pinfunction "S_H2") (pintype "passive"))
      (node (ref "P302") (pin "H3") (pinfunction "S_H3") (pintype "passive"))
      (node (ref "P302") (pin "H4") (pinfunction "S_H4") (pintype "passive"))
      (node (ref "P302") (pin "H5") (pinfunction "S_H5") (pintype "passive"))
      (node (ref "P302") (pin "H6") (pinfunction "S_H6") (pintype "passive"))
      (node (ref "P302") (pin "H7") (pinfunction "S_H7") (pintype "passive"))
      (node (ref "P302") (pin "H8") (pinfunction "S_H8") (pintype "passive"))
      (node (ref "P302") (pin "H9") (pinfunction "S_H9") (pintype "passive"))
      (node (ref "P302") (pin "PAD") (pinfunction "S_PAD") (pintype "passive"))
      (node (ref "Q405") (pin "S1") (pinfunction "S1_S1") (pintype "bidirectional"))
      (node (ref "Q405") (pin "S2") (pinfunction "S1_S2") (pintype "bidirectional"))
      (node (ref "Q405") (pin "S3") (pinfunction "S1_S3") (pintype "bidirectional"))
      (node (ref "Q405") (pin "S4") (pinfunction "S1_S4") (pintype "bidirectional"))
      (node (ref "Q405") (pin "S5") (pinfunction "S1_S5") (pintype "bidirectional"))
      (node (ref "Q406") (pin "S1") (pinfunction "S1_S1") (pintype "bidirectional"))
      (node (ref "Q406") (pin "S2") (pinfunction "S1_S2") (pintype "bidirectional"))
      (node (ref "Q406") (pin "S3") (pinfunction "S1_S3") (pintype "bidirectional"))
      (node (ref "Q406") (pin "S4") (pinfunction "S1_S4") (pintype "bidirectional"))
      (node (ref "Q406") (pin "S5") (pinfunction "S1_S5") (pintype "bidirectional"))
      (node (ref "Q407") (pin "S1") (pinfunction "S1_S1") (pintype "bidirectional"))
      (node (ref "Q407") (pin "S2") (pinfunction "S1_S2") (pintype "bidirectional"))
      (node (ref "Q407") (pin "S3") (pinfunction "S1_S3") (pintype "bidirectional"))
      (node (ref "Q407") (pin "S4") (pinfunction "S1_S4") (pintype "bidirectional"))
      (node (ref "Q407") (pin "S5") (pinfunction "S1_S5") (pintype "bidirectional"))
      (node (ref "Q408") (pin "S1") (pinfunction "S1_S1") (pintype "bidirectional"))
      (node (ref "Q408") (pin "S2") (pinfunction "S1_S2") (pintype "bidirectional"))
      (node (ref "Q408") (pin "S3") (pinfunction "S1_S3") (pintype "bidirectional"))
      (node (ref "Q408") (pin "S4") (pinfunction "S1_S4") (pintype "bidirectional"))
      (node (ref "Q408") (pin "S5") (pinfunction "S1_S5") (pintype "bidirectional"))
      (node (ref "Q409") (pin "S1") (pinfunction "S1_S1") (pintype "bidirectional"))
      (node (ref "Q409") (pin "S2") (pinfunction "S1_S2") (pintype "bidirectional"))
      (node (ref "Q409") (pin "S3") (pinfunction "S1_S3") (pintype "bidirectional"))
      (node (ref "Q409") (pin "S4") (pinfunction "S1_S4") (pintype "bidirectional"))
      (node (ref "Q409") (pin "S5") (pinfunction "S1_S5") (pintype "bidirectional"))
      (node (ref "R104") (pin "P$1") (pinfunction "P$1_P$1") (pintype "bidirectional"))
      (node (ref "R105") (pin "P$1") (pinfunction "P$1_P$1") (pintype "bidirectional"))
      (node (ref "R107") (pin "P$1") (pinfunction "P$1_P$1") (pintype "bidirectional"))
      (node (ref "R108") (pin "P$1") (pinfunction "P$1_P$1") (pintype "bidirectional"))
      (node (ref "R110") (pin "P$1") (pinfunction "P$1_P$1") (pintype "bidirectional"))
      (node (ref "R114") (pin "P$2") (pinfunction "P$2_P$2") (pintype "bidirectional"))
      (node (ref "R116") (pin "P$1") (pinfunction "P$1_P$1") (pintype "bidirectional"))
      (node (ref "R118") (pin "P$1") (pinfunction "P$1_P$1") (pintype "bidirectional"))
      (node (ref "R121") (pin "P$1") (pinfunction "P$1_P$1") (pintype "bidirectional"))
      (node (ref "R302") (pin "P$1") (pinfunction "P$1_P$1") (pintype "bidirectional"))
      (node (ref "R304") (pin "P$1") (pinfunction "P$1_P$1") (pintype "bidirectional"))
      (node (ref "R401") (pin "P$1") (pinfunction "P$1_P$1") (pintype "bidirectional"))
      (node (ref "R402") (pin "P$1") (pinfunction "P$1_P$1") (pintype "bidirectional"))
      (node (ref "R403") (pin "P$1") (pinfunction "P$1_P$1") (pintype "bidirectional"))
      (node (ref "R404") (pin "P$1") (pinfunction "P$1_P$1") (pintype "bidirectional"))
      (node (ref "R405") (pin "P$1") (pinfunction "P$1_P$1") (pintype "bidirectional"))
      (node (ref "R406") (pin "P$1") (pinfunction "P$1_P$1") (pintype "bidirectional"))
      (node (ref "R407") (pin "P$1") (pinfunction "P$1_P$1") (pintype "bidirectional"))
      (node (ref "R408") (pin "P$1") (pinfunction "P$1_P$1") (pintype "bidirectional"))
      (node (ref "R428") (pin "P$1") (pinfunction "P$1_P$1") (pintype "bidirectional"))
      (node (ref "R430") (pin "P$1") (pinfunction "P$1_P$1") (pintype "bidirectional"))
      (node (ref "R505") (pin "P$1") (pinfunction "P$1_P$1") (pintype "bidirectional"))
      (node (ref "R507") (pin "P$2") (pinfunction "P$2_P$2") (pintype "bidirectional"))
      (node (ref "R510") (pin "P$1") (pinfunction "P$1_P$1") (pintype "bidirectional"))
      (node (ref "R511") (pin "P$1") (pinfunction "P$1_P$1") (pintype "bidirectional"))
      (node (ref "U101") (pin "3") (pinfunction "GND_3") (pintype "bidirectional"))
      (node (ref "U102") (pin "14") (pinfunction "GND_14") (pintype "bidirectional"))
      (node (ref "U102") (pin "24") (pinfunction "GNDA_24") (pintype "bidirectional"))
      (node (ref "U102") (pin "3") (pinfunction "GND_3") (pintype "bidirectional"))
      (node (ref "U102") (pin "44") (pinfunction "GND_44") (pintype "bidirectional"))
      (node (ref "U102") (pin "53") (pinfunction "PLL_GND_53") (pintype "bidirectional"))
      (node (ref "U102") (pin "54") (pinfunction "TEST_54") (pintype "bidirectional"))
      (node (ref "U102") (pin "62") (pinfunction "GND_62") (pintype "bidirectional"))
      (node (ref "U102") (pin "73") (pinfunction "GND_73") (pintype "bidirectional"))
      (node (ref "U102") (pin "PAD") (pinfunction "GNDP_PAD") (pintype "bidirectional"))
      (node (ref "U201") (pin "2") (pinfunction "GND_2") (pintype "bidirectional"))
      (node (ref "U202") (pin "2") (pinfunction "GND_2") (pintype "bidirectional"))
      (node (ref "U203") (pin "2") (pinfunction "GND_2") (pintype "bidirectional"))
      (node (ref "U204") (pin "2") (pinfunction "GND_2") (pintype "bidirectional"))
      (node (ref "U205") (pin "4") (pinfunction "GND_4") (pintype "bidirectional"))
      (node (ref "U206") (pin "4") (pinfunction "GND_4") (pintype "bidirectional"))
      (node (ref "U207") (pin "4") (pinfunction "GND_4") (pintype "bidirectional"))
      (node (ref "U208") (pin "4") (pinfunction "GND_4") (pintype "bidirectional"))
      (node (ref "U301") (pin "2") (pinfunction "GND_2") (pintype "bidirectional"))
      (node (ref "U301") (pin "4") (pinfunction "SHDN_4") (pintype "bidirectional"))
      (node (ref "U301") (pin "6") (pinfunction "GND_6") (pintype "bidirectional"))
      (node (ref "U301") (pin "7") (pinfunction "GND_7") (pintype "bidirectional"))
      (node (ref "U302") (pin "5") (pinfunction "GND_5") (pintype "bidirectional"))
      (node (ref "U302") (pin "6") (pinfunction "GND_6") (pintype "bidirectional"))
      (node (ref "U302") (pin "7") (pinfunction "GND_7") (pintype "bidirectional"))
      (node (ref "U302") (pin "8") (pinfunction "GND_8") (pintype "bidirectional"))
      (node (ref "U303") (pin "5") (pinfunction "GND_5") (pintype "bidirectional"))
      (node (ref "U303") (pin "6") (pinfunction "GND_6") (pintype "bidirectional"))
      (node (ref "U303") (pin "7") (pinfunction "GND_7") (pintype "bidirectional"))
      (node (ref "U303") (pin "8") (pinfunction "GND_8") (pintype "bidirectional"))
      (node (ref "U401") (pin "4") (pinfunction "GNDI_4") (pintype "bidirectional"))
      (node (ref "U401") (pin "9") (pinfunction "GNB_9") (pintype "bidirectional"))
      (node (ref "U402") (pin "4") (pinfunction "GNDI_4") (pintype "bidirectional"))
      (node (ref "U402") (pin "9") (pinfunction "GNB_9") (pintype "bidirectional"))
      (node (ref "U403") (pin "4") (pinfunction "GNDI_4") (pintype "bidirectional"))
      (node (ref "U403") (pin "9") (pinfunction "GNB_9") (pintype "bidirectional"))
      (node (ref "U404") (pin "4") (pinfunction "GNDI_4") (pintype "bidirectional"))
      (node (ref "U404") (pin "9") (pinfunction "GNB_9") (pintype "bidirectional"))
      (node (ref "U405") (pin "2") (pinfunction "P$1_2") (pintype "bidirectional"))
      (node (ref "U405") (pin "3") (pinfunction "P$1_3") (pintype "bidirectional"))
      (node (ref "U406") (pin "2") (pinfunction "P$1_2") (pintype "bidirectional"))
      (node (ref "U406") (pin "3") (pinfunction "P$1_3") (pintype "bidirectional"))
      (node (ref "U407") (pin "3") (pinfunction "CA_3") (pintype "bidirectional"))
      (node (ref "U407") (pin "5") (pinfunction "GNB_5") (pintype "bidirectional"))
      (node (ref "U501") (pin "2") (pinfunction "GND_2") (pintype "bidirectional"))
      (node (ref "U501") (pin "PAD") (pinfunction "GNDP_PAD") (pintype "bidirectional"))
    )
    (net (code "32") (name "HALL_UX") (class "Default")
      (node (ref "U102") (pin "38") (pinfunction "HALL_UX_38") (pintype "bidirectional"))
      (node (ref "U207") (pin "2") (pinfunction "Y_2") (pintype "output"))
    )
    (net (code "33") (name "HALL_V") (class "Default")
      (node (ref "U102") (pin "37") (pinfunction "HALL_V_37") (pintype "bidirectional"))
      (node (ref "U207") (pin "5") (pinfunction "Y_5") (pintype "output"))
    )
    (net (code "34") (name "HALL_WY") (class "Default")
      (node (ref "U102") (pin "36") (pinfunction "HALL_WY_36") (pintype "bidirectional"))
      (node (ref "U207") (pin "7") (pinfunction "Y_7") (pintype "output"))
    )
    (net (code "35") (name "INT") (class "Default")
      (node (ref "J501") (pin "5") (pinfunction "S_5") (pintype "passive"))
      (node (ref "JP507") (pin "2") (pinfunction "2_2") (pintype "passive"))
      (node (ref "U102") (pin "12") (pinfunction "STATUS_12") (pintype "bidirectional"))
    )
    (net (code "36") (name "MISO") (class "Default")
      (node (ref "J501") (pin "4") (pinfunction "S_4") (pintype "passive"))
      (node (ref "JP501") (pin "2") (pinfunction "2_2") (pintype "passive"))
      (node (ref "U102") (pin "9") (pinfunction "SPI_MISO_9") (pintype "bidirectional"))
    )
    (net (code "37") (name "MOSI") (class "Default")
      (node (ref "J501") (pin "3") (pinfunction "S_3") (pintype "passive"))
      (node (ref "JP502") (pin "2") (pinfunction "2_2") (pintype "passive"))
      (node (ref "U102") (pin "8") (pinfunction "SPI_MOSI_8") (pintype "bidirectional"))
    )
    (net (code "38") (name "Net-(C307-AN)") (class "Default")
      (node (ref "C305") (pin "P$1") (pinfunction "P$1_P$1") (pintype "bidirectional"))
      (node (ref "C307") (pin "+") (pinfunction "AN_+") (pintype "bidirectional"))
      (node (ref "L301") (pin "2") (pinfunction "P$2_2") (pintype "bidirectional"))
      (node (ref "R303") (pin "P$2") (pinfunction "P$2_P$2") (pintype "bidirectional"))
      (node (ref "R305") (pin "P$2") (pinfunction "P$2_P$2") (pintype "bidirectional"))
      (node (ref "U302") (pin "1") (pinfunction "EN_1") (pintype "bidirectional"))
      (node (ref "U302") (pin "2") (pinfunction "VIN_2") (pintype "bidirectional"))
      (node (ref "U303") (pin "1") (pinfunction "EN_1") (pintype "bidirectional"))
      (node (ref "U303") (pin "2") (pinfunction "VIN_2") (pintype "bidirectional"))
    )
    (net (code "39") (name "Net-(D101-3)") (class "Default")
      (node (ref "C118") (pin "P$1") (pinfunction "P$1_P$1") (pintype "bidirectional"))
      (node (ref "D101") (pin "P$3") (pinfunction "3_P$3") (pintype "bidirectional"))
      (node (ref "R116") (pin "P$2") (pinfunction "P$2_P$2") (pintype "bidirectional"))
      (node (ref "R119") (pin "P$1") (pinfunction "P$1_P$1") (pintype "bidirectional"))
      (node (ref "U102") (pin "20") (pinfunction "ADC_VM_20") (pintype "bidirectional"))
    )
    (net (code "40") (name "Net-(D302-AN)") (class "Default")
      (node (ref "D302") (pin "A") (pinfunction "AN_A") (pintype "bidirectional"))
      (node (ref "R305") (pin "P$1") (pinfunction "P$1_P$1") (pintype "bidirectional"))
      (node (ref "U302") (pin "4") (pinfunction "FLG_4") (pintype "bidirectional"))
      (node (ref "U303") (pin "4") (pinfunction "FLG_4") (pintype "bidirectional"))
    )
    (net (code "41") (name "Net-(D401-PadA)") (class "Default")
      (node (ref "D401") (pin "A") (pinfunction "A_A") (pintype "passive"))
      (node (ref "R409") (pin "P$2") (pinfunction "P$2_P$2") (pintype "bidirectional"))
    )
    (net (code "42") (name "Net-(D402-PadA)") (class "Default")
      (node (ref "D402") (pin "A") (pinfunction "A_A") (pintype "passive"))
      (node (ref "R410") (pin "P$2") (pinfunction "P$2_P$2") (pintype "bidirectional"))
    )
    (net (code "43") (name "Net-(D403-PadA)") (class "Default")
      (node (ref "D403") (pin "A") (pinfunction "A_A") (pintype "passive"))
      (node (ref "R411") (pin "P$2") (pinfunction "P$2_P$2") (pintype "bidirectional"))
    )
    (net (code "44") (name "Net-(D404-PadA)") (class "Default")
      (node (ref "D404") (pin "A") (pinfunction "A_A") (pintype "passive"))
      (node (ref "R412") (pin "P$2") (pinfunction "P$2_P$2") (pintype "bidirectional"))
    )
    (net (code "45") (name "Net-(D501-AN)") (class "Default")
      (node (ref "D501") (pin "A") (pinfunction "AN_A") (pintype "bidirectional"))
      (node (ref "R502") (pin "P$1") (pinfunction "P$1_P$1") (pintype "bidirectional"))
    )
    (net (code "46") (name "Net-(D501-CA)") (class "Default")
      (node (ref "D501") (pin "C") (pinfunction "CA_C") (pintype "bidirectional"))
      (node (ref "U501") (pin "14") (pinfunction "(GPIO0-TXT)GPIO7-~{CS7}_14") (pintype "bidirectional"))
    )
    (net (code "47") (name "Net-(D502-AN)") (class "Default")
      (node (ref "D502") (pin "A") (pinfunction "AN_A") (pintype "bidirectional"))
      (node (ref "R503") (pin "P$1") (pinfunction "P$1_P$1") (pintype "bidirectional"))
    )
    (net (code "48") (name "Net-(D502-CA)") (class "Default")
      (node (ref "D502") (pin "C") (pinfunction "CA_C") (pintype "bidirectional"))
      (node (ref "U501") (pin "13") (pinfunction "(GPIO1-RXT)GPIO8-~{CS8}-SPIACT_13") (pintype "bidirectional"))
    )
    (net (code "49") (name "Net-(D503-Pad4)") (class "Default")
      (node (ref "D503") (pin "4") (pinfunction "4_4") (pintype "bidirectional"))
      (node (ref "J503") (pin "VBUS") (pinfunction "VBUS_VBUS") (pintype "bidirectional"))
      (node (ref "R506") (pin "P$1") (pinfunction "P$1_P$1") (pintype "bidirectional"))
    )
    (net (code "50") (name "Net-(J201B-S)") (class "Default")
      (node (ref "J201") (pin "2") (pinfunction "S_2") (pintype "passive"))
      (node (ref "R201") (pin "P$1") (pinfunction "P$1_P$1") (pintype "bidirectional"))
    )
    (net (code "51") (name "Net-(J201C-S)") (class "Default")
      (node (ref "J201") (pin "3") (pinfunction "S_3") (pintype "passive"))
      (node (ref "R202") (pin "P$1") (pinfunction "P$1_P$1") (pintype "bidirectional"))
    )
    (net (code "52") (name "Net-(J201D-S)") (class "Default")
      (node (ref "J201") (pin "4") (pinfunction "S_4") (pintype "passive"))
      (node (ref "R203") (pin "P$1") (pinfunction "P$1_P$1") (pintype "bidirectional"))
    )
    (net (code "53") (name "Net-(J202B-S)") (class "Default")
      (node (ref "J202") (pin "2") (pinfunction "S_2") (pintype "passive"))
      (node (ref "R204") (pin "P$1") (pinfunction "P$1_P$1") (pintype "bidirectional"))
    )
    (net (code "54") (name "Net-(J202C-S)") (class "Default")
      (node (ref "J202") (pin "3") (pinfunction "S_3") (pintype "passive"))
      (node (ref "R205") (pin "P$1") (pinfunction "P$1_P$1") (pintype "bidirectional"))
    )
    (net (code "55") (name "Net-(J202D-S)") (class "Default")
      (node (ref "J202") (pin "4") (pinfunction "S_4") (pintype "passive"))
      (node (ref "R206") (pin "P$1") (pinfunction "P$1_P$1") (pintype "bidirectional"))
    )
    (net (code "56") (name "Net-(J203B-S)") (class "Default")
      (node (ref "J203") (pin "2") (pinfunction "S_2") (pintype "passive"))
      (node (ref "R207") (pin "P$1") (pinfunction "P$1_P$1") (pintype "bidirectional"))
    )
    (net (code "57") (name "Net-(J203C-S)") (class "Default")
      (node (ref "J203") (pin "3") (pinfunction "S_3") (pintype "passive"))
      (node (ref "R208") (pin "P$1") (pinfunction "P$1_P$1") (pintype "bidirectional"))
    )
    (net (code "58") (name "Net-(J203D-S)") (class "Default")
      (node (ref "J203") (pin "4") (pinfunction "S_4") (pintype "passive"))
      (node (ref "R209") (pin "P$1") (pinfunction "P$1_P$1") (pintype "bidirectional"))
    )
    (net (code "59") (name "Net-(J204B-S)") (class "Default")
      (node (ref "J204") (pin "2") (pinfunction "S_2") (pintype "passive"))
      (node (ref "R210") (pin "P$1") (pinfunction "P$1_P$1") (pintype "bidirectional"))
    )
    (net (code "60") (name "Net-(J204C-S)") (class "Default")
      (node (ref "J204") (pin "3") (pinfunction "S_3") (pintype "passive"))
      (node (ref "R211") (pin "P$1") (pinfunction "P$1_P$1") (pintype "bidirectional"))
    )
    (net (code "61") (name "Net-(J204D-S)") (class "Default")
      (node (ref "J204") (pin "4") (pinfunction "S_4") (pintype "passive"))
      (node (ref "R212") (pin "P$1") (pinfunction "P$1_P$1") (pintype "bidirectional"))
    )
    (net (code "62") (name "Net-(J205B-S)") (class "Default")
      (node (ref "J205") (pin "2") (pinfunction "S_2") (pintype "passive"))
      (node (ref "R213") (pin "P$1") (pinfunction "P$1_P$1") (pintype "bidirectional"))
    )
    (net (code "63") (name "Net-(J205C-S)") (class "Default")
      (node (ref "J205") (pin "3") (pinfunction "S_3") (pintype "passive"))
      (node (ref "R218") (pin "P$1") (pinfunction "P$1_P$1") (pintype "bidirectional"))
    )
    (net (code "64") (name "Net-(J205D-S)") (class "Default")
      (node (ref "J205") (pin "4") (pinfunction "S_4") (pintype "passive"))
      (node (ref "R227") (pin "P$1") (pinfunction "P$1_P$1") (pintype "bidirectional"))
    )
    (net (code "65") (name "Net-(J403B-S)") (class "Default")
      (node (ref "J403") (pin "2") (pinfunction "S_2") (pintype "passive"))
      (node (ref "P406") (pin "H1") (pinfunction "S_H1") (pintype "passive"))
      (node (ref "P406") (pin "H10") (pinfunction "S_H10") (pintype "passive"))
      (node (ref "P406") (pin "H11") (pinfunction "S_H11") (pintype "passive"))
      (node (ref "P406") (pin "H12") (pinfunction "S_H12") (pintype "passive"))
      (node (ref "P406") (pin "H2") (pinfunction "S_H2") (pintype "passive"))
      (node (ref "P406") (pin "H3") (pinfunction "S_H3") (pintype "passive"))
      (node (ref "P406") (pin "H4") (pinfunction "S_H4") (pintype "passive"))
      (node (ref "P406") (pin "H5") (pinfunction "S_H5") (pintype "passive"))
      (node (ref "P406") (pin "H6") (pinfunction "S_H6") (pintype "passive"))
      (node (ref "P406") (pin "H7") (pinfunction "S_H7") (pintype "passive"))
      (node (ref "P406") (pin "H8") (pinfunction "S_H8") (pintype "passive"))
      (node (ref "P406") (pin "H9") (pinfunction "S_H9") (pintype "passive"))
      (node (ref "P406") (pin "PAD") (pinfunction "S_PAD") (pintype "passive"))
      (node (ref "Q409") (pin "D1") (pinfunction "D1_D1") (pintype "bidirectional"))
      (node (ref "Q409") (pin "D2") (pinfunction "D1_D2") (pintype "bidirectional"))
      (node (ref "Q409") (pin "D3") (pinfunction "D1_D3") (pintype "bidirectional"))
      (node (ref "Q409") (pin "D4") (pinfunction "D1_D4") (pintype "bidirectional"))
    )
    (net (code "66") (name "Net-(J504A-S)") (class "Default")
      (node (ref "J504") (pin "1") (pinfunction "S_1") (pintype "passive"))
      (node (ref "R504") (pin "P$1") (pinfunction "P$1_P$1") (pintype "bidirectional"))
    )
    (net (code "67") (name "Net-(J506A-S)") (class "Default")
      (node (ref "J506") (pin "1") (pinfunction "S_1") (pintype "passive"))
      (node (ref "R508") (pin "P$1") (pinfunction "P$1_P$1") (pintype "bidirectional"))
    )
    (net (code "68") (name "Net-(J506B-S)") (class "Default")
      (node (ref "J506") (pin "2") (pinfunction "S_2") (pintype "passive"))
      (node (ref "R509") (pin "P$1") (pinfunction "P$1_P$1") (pintype "bidirectional"))
    )
    (net (code "69") (name "Net-(L301-P$1)") (class "Default")
      (node (ref "D301") (pin "C") (pinfunction "C_C") (pintype "bidirectional"))
      (node (ref "L301") (pin "1") (pinfunction "P$1_1") (pintype "bidirectional"))
      (node (ref "U301") (pin "8") (pinfunction "SW_8") (pintype "bidirectional"))
    )
    (net (code "70") (name "Net-(Q401-G1)") (class "Default")
      (node (ref "Q401") (pin "G") (pinfunction "G1_G") (pintype "bidirectional"))
      (node (ref "R413") (pin "P$2") (pinfunction "P$2_P$2") (pintype "bidirectional"))
    )
    (net (code "71") (name "Net-(Q402-G1)") (class "Default")
      (node (ref "Q402") (pin "G") (pinfunction "G1_G") (pintype "bidirectional"))
      (node (ref "R414") (pin "P$2") (pinfunction "P$2_P$2") (pintype "bidirectional"))
    )
    (net (code "72") (name "Net-(Q403-G1)") (class "Default")
      (node (ref "Q403") (pin "G") (pinfunction "G1_G") (pintype "bidirectional"))
      (node (ref "R415") (pin "P$2") (pinfunction "P$2_P$2") (pintype "bidirectional"))
    )
    (net (code "73") (name "Net-(Q404-G1)") (class "Default")
      (node (ref "Q404") (pin "G") (pinfunction "G1_G") (pintype "bidirectional"))
      (node (ref "R416") (pin "P$2") (pinfunction "P$2_P$2") (pintype "bidirectional"))
    )
    (net (code "74") (name "Net-(Q405-G1)") (class "Default")
      (node (ref "Q405") (pin "G") (pinfunction "G1_G") (pintype "bidirectional"))
      (node (ref "R417") (pin "P$2") (pinfunction "P$2_P$2") (pintype "bidirectional"))
    )
    (net (code "75") (name "Net-(Q406-G1)") (class "Default")
      (node (ref "Q406") (pin "G") (pinfunction "G1_G") (pintype "bidirectional"))
      (node (ref "R418") (pin "P$2") (pinfunction "P$2_P$2") (pintype "bidirectional"))
    )
    (net (code "76") (name "Net-(Q407-G1)") (class "Default")
      (node (ref "Q407") (pin "G") (pinfunction "G1_G") (pintype "bidirectional"))
      (node (ref "R419") (pin "P$2") (pinfunction "P$2_P$2") (pintype "bidirectional"))
    )
    (net (code "77") (name "Net-(Q408-G1)") (class "Default")
      (node (ref "Q408") (pin "G") (pinfunction "G1_G") (pintype "bidirectional"))
      (node (ref "R420") (pin "P$2") (pinfunction "P$2_P$2") (pintype "bidirectional"))
    )
    (net (code "78") (name "Net-(Q409-G1)") (class "Default")
      (node (ref "Q409") (pin "G") (pinfunction "G1_G") (pintype "bidirectional"))
      (node (ref "R431") (pin "P$2") (pinfunction "P$2_P$2") (pintype "bidirectional"))
    )
    (net (code "79") (name "Net-(R421-PadSENSE+)") (class "Default")
      (node (ref "R421") (pin "SENSE+") (pinfunction "SENSE+_SENSE+") (pintype "bidirectional"))
      (node (ref "R424") (pin "P$1") (pinfunction "P$1_P$1") (pintype "bidirectional"))
    )
    (net (code "80") (name "Net-(R421-PadSENSE-)") (class "Default")
      (node (ref "R421") (pin "SENSE-") (pinfunction "SENSE-_SENSE-") (pintype "bidirectional"))
      (node (ref "R423") (pin "P$1") (pinfunction "P$1_P$1") (pintype "bidirectional"))
    )
    (net (code "81") (name "Net-(R422-PadSENSE+)") (class "Default")
      (node (ref "R422") (pin "SENSE+") (pinfunction "SENSE+_SENSE+") (pintype "bidirectional"))
      (node (ref "R426") (pin "P$1") (pinfunction "P$1_P$1") (pintype "bidirectional"))
    )
    (net (code "82") (name "Net-(R422-PadSENSE-)") (class "Default")
      (node (ref "R422") (pin "SENSE-") (pinfunction "SENSE-_SENSE-") (pintype "bidirectional"))
      (node (ref "R425") (pin "P$1") (pinfunction "P$1_P$1") (pintype "bidirectional"))
    )
    (net (code "83") (name "Net-(R431-PadP$1)") (class "Default")
      (node (ref "R431") (pin "P$1") (pinfunction "P$1_P$1") (pintype "bidirectional"))
      (node (ref "U407") (pin "6") (pinfunction "VO_6") (pintype "bidirectional"))
      (node (ref "U407") (pin "7") (pinfunction "VO_7") (pintype "bidirectional"))
    )
    (net (code "84") (name "Net-(U101-EN)") (class "Default")
      (node (ref "R101") (pin "P$1") (pinfunction "P$1_P$1") (pintype "bidirectional"))
      (node (ref "U101") (pin "1") (pinfunction "EN_1") (pintype "bidirectional"))
    )
    (net (code "85") (name "Net-(U101-OUT)") (class "Default")
      (node (ref "U101") (pin "4") (pinfunction "OUT_4") (pintype "bidirectional"))
      (node (ref "U102") (pin "51") (pinfunction "CLK_51") (pintype "bidirectional"))
    )
    (net (code "86") (name "Net-(U102A-AGPI_A)") (class "Default")
      (node (ref "C114") (pin "P$1") (pinfunction "P$1_P$1") (pintype "bidirectional"))
      (node (ref "R111") (pin "P$1") (pinfunction "P$1_P$1") (pintype "bidirectional"))
      (node (ref "U102") (pin "21") (pinfunction "AGPI_A_21") (pintype "bidirectional"))
    )
    (net (code "87") (name "Net-(U102A-AGPI_B)") (class "Default")
      (node (ref "C115") (pin "P$1") (pinfunction "P$1_P$1") (pintype "bidirectional"))
      (node (ref "R112") (pin "P$2") (pinfunction "P$2_P$2") (pintype "bidirectional"))
      (node (ref "U102") (pin "22") (pinfunction "AGPI_B_22") (pintype "bidirectional"))
    )
    (net (code "88") (name "Net-(U102B-~{RST})") (class "Default")
      (node (ref "R102") (pin "P$2") (pinfunction "P$2_P$2") (pintype "bidirectional"))
      (node (ref "U102") (pin "50") (pinfunction "~{RST}_50") (pintype "bidirectional"))
    )
    (net (code "89") (name "Net-(U102D-ADC_I0_NEG)") (class "Default")
      (node (ref "R117") (pin "P$1") (pinfunction "P$1_P$1") (pintype "bidirectional"))
      (node (ref "R118") (pin "P$2") (pinfunction "P$2_P$2") (pintype "bidirectional"))
      (node (ref "U102") (pin "17") (pinfunction "ADC_I0_NEG_17") (pintype "bidirectional"))
    )
    (net (code "90") (name "Net-(U102D-ADC_I0_POS)") (class "Default")
      (node (ref "C116") (pin "P$1") (pinfunction "P$1_P$1") (pintype "bidirectional"))
      (node (ref "R113") (pin "P$1") (pinfunction "P$1_P$1") (pintype "bidirectional"))
      (node (ref "U102") (pin "16") (pinfunction "ADC_I0_POS_16") (pintype "bidirectional"))
    )
    (net (code "91") (name "Net-(U102D-ADC_I1_NEG)") (class "Default")
      (node (ref "R120") (pin "P$1") (pinfunction "P$1_P$1") (pintype "bidirectional"))
      (node (ref "R121") (pin "P$2") (pinfunction "P$2_P$2") (pintype "bidirectional"))
      (node (ref "U102") (pin "19") (pinfunction "ADC_I1_NEG_19") (pintype "bidirectional"))
    )
    (net (code "92") (name "Net-(U102D-ADC_I1_POS)") (class "Default")
      (node (ref "C117") (pin "P$1") (pinfunction "P$1_P$1") (pintype "bidirectional"))
      (node (ref "R115") (pin "P$1") (pinfunction "P$1_P$1") (pintype "bidirectional"))
      (node (ref "U102") (pin "18") (pinfunction "ADC_I1_POS_18") (pintype "bidirectional"))
    )
    (net (code "93") (name "Net-(U102D-AENC_UX_NEG)") (class "Default")
      (node (ref "R103") (pin "P$1") (pinfunction "P$1_P$1") (pintype "bidirectional"))
      (node (ref "R104") (pin "P$2") (pinfunction "P$2_P$2") (pintype "bidirectional"))
      (node (ref "U102") (pin "26") (pinfunction "AENC_UX_NEG_26") (pintype "bidirectional"))
    )
    (net (code "94") (name "Net-(U102D-AENC_VN_NEG)") (class "Default")
      (node (ref "R106") (pin "P$1") (pinfunction "P$1_P$1") (pintype "bidirectional"))
      (node (ref "R107") (pin "P$2") (pinfunction "P$2_P$2") (pintype "bidirectional"))
      (node (ref "U102") (pin "28") (pinfunction "AENC_VN_NEG_28") (pintype "bidirectional"))
    )
    (net (code "95") (name "Net-(U102D-AENC_WY_NEG)") (class "Default")
      (node (ref "R109") (pin "P$1") (pinfunction "P$1_P$1") (pintype "bidirectional"))
      (node (ref "R110") (pin "P$2") (pinfunction "P$2_P$2") (pintype "bidirectional"))
      (node (ref "U102") (pin "30") (pinfunction "AENC_WY_NEG_30") (pintype "bidirectional"))
    )
    (net (code "96") (name "Net-(U102D-PWM_IDLE_H)") (class "Default")
      (node (ref "R105") (pin "P$2") (pinfunction "P$2_P$2") (pintype "bidirectional"))
      (node (ref "U102") (pin "59") (pinfunction "PWM_IDLE_H_59") (pintype "bidirectional"))
    )
    (net (code "97") (name "Net-(U102D-PWM_IDLE_L)") (class "Default")
      (node (ref "R108") (pin "P$2") (pinfunction "P$2_P$2") (pintype "bidirectional"))
      (node (ref "U102") (pin "60") (pinfunction "PWM_IDLE_L_60") (pintype "bidirectional"))
    )
    (net (code "98") (name "Net-(U201-1)") (class "Default")
      (node (ref "C206") (pin "P$1") (pinfunction "P$1_P$1") (pintype "bidirectional"))
      (node (ref "R201") (pin "P$2") (pinfunction "P$2_P$2") (pintype "bidirectional"))
      (node (ref "R214") (pin "P$2") (pinfunction "P$2_P$2") (pintype "bidirectional"))
      (node (ref "U201") (pin "6") (pinfunction "1_6") (pintype "bidirectional"))
      (node (ref "U205") (pin "1") (pinfunction "A_1") (pintype "input"))
    )
    (net (code "99") (name "Net-(U201-2)") (class "Default")
      (node (ref "C218") (pin "P$1") (pinfunction "P$1_P$1") (pintype "bidirectional"))
      (node (ref "R203") (pin "P$2") (pinfunction "P$2_P$2") (pintype "bidirectional"))
      (node (ref "R223") (pin "P$2") (pinfunction "P$2_P$2") (pintype "bidirectional"))
      (node (ref "U201") (pin "1") (pinfunction "2_1") (pintype "bidirectional"))
      (node (ref "U205") (pin "6") (pinfunction "A_6") (pintype "input"))
    )
    (net (code "100") (name "Net-(U202-1)") (class "Default")
      (node (ref "C207") (pin "P$1") (pinfunction "P$1_P$1") (pintype "bidirectional"))
      (node (ref "R204") (pin "P$2") (pinfunction "P$2_P$2") (pintype "bidirectional"))
      (node (ref "R215") (pin "P$2") (pinfunction "P$2_P$2") (pintype "bidirectional"))
      (node (ref "U202") (pin "6") (pinfunction "1_6") (pintype "bidirectional"))
      (node (ref "U206") (pin "1") (pinfunction "A_1") (pintype "input"))
    )
    (net (code "101") (name "Net-(U202-2)") (class "Default")
      (node (ref "C219") (pin "P$1") (pinfunction "P$1_P$1") (pintype "bidirectional"))
      (node (ref "R206") (pin "P$2") (pinfunction "P$2_P$2") (pintype "bidirectional"))
      (node (ref "R224") (pin "P$2") (pinfunction "P$2_P$2") (pintype "bidirectional"))
      (node (ref "U202") (pin "1") (pinfunction "2_1") (pintype "bidirectional"))
      (node (ref "U206") (pin "6") (pinfunction "A_6") (pintype "input"))
    )
    (net (code "102") (name "Net-(U203-1)") (class "Default")
      (node (ref "C208") (pin "P$1") (pinfunction "P$1_P$1") (pintype "bidirectional"))
      (node (ref "R207") (pin "P$2") (pinfunction "P$2_P$2") (pintype "bidirectional"))
      (node (ref "R216") (pin "P$2") (pinfunction "P$2_P$2") (pintype "bidirectional"))
      (node (ref "U203") (pin "6") (pinfunction "1_6") (pintype "bidirectional"))
      (node (ref "U207") (pin "1") (pinfunction "A_1") (pintype "input"))
    )
    (net (code "103") (name "Net-(U203-2)") (class "Default")
      (node (ref "C220") (pin "P$1") (pinfunction "P$1_P$1") (pintype "bidirectional"))
      (node (ref "R209") (pin "P$2") (pinfunction "P$2_P$2") (pintype "bidirectional"))
      (node (ref "R225") (pin "P$2") (pinfunction "P$2_P$2") (pintype "bidirectional"))
      (node (ref "U203") (pin "1") (pinfunction "2_1") (pintype "bidirectional"))
      (node (ref "U207") (pin "6") (pinfunction "A_6") (pintype "input"))
    )
    (net (code "104") (name "Net-(U204-1)") (class "Default")
      (node (ref "C209") (pin "P$1") (pinfunction "P$1_P$1") (pintype "bidirectional"))
      (node (ref "R210") (pin "P$2") (pinfunction "P$2_P$2") (pintype "bidirectional"))
      (node (ref "R217") (pin "P$2") (pinfunction "P$2_P$2") (pintype "bidirectional"))
      (node (ref "U204") (pin "6") (pinfunction "1_6") (pintype "bidirectional"))
      (node (ref "U208") (pin "1") (pinfunction "A_1") (pintype "input"))
    )
    (net (code "105") (name "Net-(U204-2)") (class "Default")
      (node (ref "C221") (pin "P$1") (pinfunction "P$1_P$1") (pintype "bidirectional"))
      (node (ref "R212") (pin "P$2") (pinfunction "P$2_P$2") (pintype "bidirectional"))
      (node (ref "R226") (pin "P$2") (pinfunction "P$2_P$2") (pintype "bidirectional"))
      (node (ref "U204") (pin "1") (pinfunction "2_1") (pintype "bidirectional"))
      (node (ref "U208") (pin "6") (pinfunction "A_6") (pintype "input"))
    )
    (net (code "106") (name "Net-(U205B-A)") (class "Default")
      (node (ref "C210") (pin "P$1") (pinfunction "P$1_P$1") (pintype "bidirectional"))
      (node (ref "R202") (pin "P$2") (pinfunction "P$2_P$2") (pintype "bidirectional"))
      (node (ref "R219") (pin "P$2") (pinfunction "P$2_P$2") (pintype "bidirectional"))
      (node (ref "U201") (pin "4") (pinfunction "4_4") (pintype "bidirectional"))
      (node (ref "U205") (pin "3") (pinfunction "A_3") (pintype "input"))
    )
    (net (code "107") (name "Net-(U206B-A)") (class "Default")
      (node (ref "C211") (pin "P$1") (pinfunction "P$1_P$1") (pintype "bidirectional"))
      (node (ref "R205") (pin "P$2") (pinfunction "P$2_P$2") (pintype "bidirectional"))
      (node (ref "R220") (pin "P$2") (pinfunction "P$2_P$2") (pintype "bidirectional"))
      (node (ref "U202") (pin "4") (pinfunction "4_4") (pintype "bidirectional"))
      (node (ref "U206") (pin "3") (pinfunction "A_3") (pintype "input"))
    )
    (net (code "108") (name "Net-(U207B-A)") (class "Default")
      (node (ref "C212") (pin "P$1") (pinfunction "P$1_P$1") (pintype "bidirectional"))
      (node (ref "R208") (pin "P$2") (pinfunction "P$2_P$2") (pintype "bidirectional"))
      (node (ref "R221") (pin "P$2") (pinfunction "P$2_P$2") (pintype "bidirectional"))
      (node (ref "U203") (pin "4") (pinfunction "4_4") (pintype "bidirectional"))
      (node (ref "U207") (pin "3") (pinfunction "A_3") (pintype "input"))
    )
    (net (code "109") (name "Net-(U208B-A)") (class "Default")
      (node (ref "C213") (pin "P$1") (pinfunction "P$1_P$1") (pintype "bidirectional"))
      (node (ref "R211") (pin "P$2") (pinfunction "P$2_P$2") (pintype "bidirectional"))
      (node (ref "R222") (pin "P$2") (pinfunction "P$2_P$2") (pintype "bidirectional"))
      (node (ref "U204") (pin "4") (pinfunction "4_4") (pintype "bidirectional"))
      (node (ref "U208") (pin "3") (pinfunction "A_3") (pintype "input"))
    )
    (net (code "110") (name "Net-(U301-FB)") (class "Default")
      (node (ref "R303") (pin "P$1") (pinfunction "P$1_P$1") (pintype "bidirectional"))
      (node (ref "R304") (pin "P$2") (pinfunction "P$2_P$2") (pintype "bidirectional"))
      (node (ref "U301") (pin "1") (pinfunction "FB_1") (pintype "bidirectional"))
    )
    (net (code "111") (name "Net-(U301-ISET)") (class "Default")
      (node (ref "R301") (pin "P$1") (pinfunction "P$1_P$1") (pintype "bidirectional"))
      (node (ref "R302") (pin "P$2") (pinfunction "P$2_P$2") (pintype "bidirectional"))
      (node (ref "U301") (pin "3") (pinfunction "ISET_3") (pintype "bidirectional"))
    )
    (net (code "112") (name "Net-(U401-VDDA)") (class "Default")
      (node (ref "C417") (pin "P$1") (pinfunction "P$1_P$1") (pintype "bidirectional"))
      (node (ref "D401") (pin "C") (pinfunction "C_C") (pintype "passive"))
      (node (ref "U401") (pin "16") (pinfunction "VDDA_16") (pintype "bidirectional"))
    )
    (net (code "113") (name "Net-(U401-VOA)") (class "Default")
      (node (ref "R413") (pin "P$1") (pinfunction "P$1_P$1") (pintype "bidirectional"))
      (node (ref "U401") (pin "15") (pinfunction "VOA_15") (pintype "bidirectional"))
    )
    (net (code "114") (name "Net-(U401-VOB)") (class "Default")
      (node (ref "R417") (pin "P$1") (pinfunction "P$1_P$1") (pintype "bidirectional"))
      (node (ref "U401") (pin "10") (pinfunction "VOB_10") (pintype "bidirectional"))
    )
    (net (code "115") (name "Net-(U402-VDDA)") (class "Default")
      (node (ref "C418") (pin "P$1") (pinfunction "P$1_P$1") (pintype "bidirectional"))
      (node (ref "D402") (pin "C") (pinfunction "C_C") (pintype "passive"))
      (node (ref "U402") (pin "16") (pinfunction "VDDA_16") (pintype "bidirectional"))
    )
    (net (code "116") (name "Net-(U402-VOA)") (class "Default")
      (node (ref "R414") (pin "P$1") (pinfunction "P$1_P$1") (pintype "bidirectional"))
      (node (ref "U402") (pin "15") (pinfunction "VOA_15") (pintype "bidirectional"))
    )
    (net (code "117") (name "Net-(U402-VOB)") (class "Default")
      (node (ref "R418") (pin "P$1") (pinfunction "P$1_P$1") (pintype "bidirectional"))
      (node (ref "U402") (pin "10") (pinfunction "VOB_10") (pintype "bidirectional"))
    )
    (net (code "118") (name "Net-(U403-VDDA)") (class "Default")
      (node (ref "C419") (pin "P$1") (pinfunction "P$1_P$1") (pintype "bidirectional"))
      (node (ref "D403") (pin "C") (pinfunction "C_C") (pintype "passive"))
      (node (ref "U403") (pin "16") (pinfunction "VDDA_16") (pintype "bidirectional"))
    )
    (net (code "119") (name "Net-(U403-VOA)") (class "Default")
      (node (ref "R415") (pin "P$1") (pinfunction "P$1_P$1") (pintype "bidirectional"))
      (node (ref "U403") (pin "15") (pinfunction "VOA_15") (pintype "bidirectional"))
    )
    (net (code "120") (name "Net-(U403-VOB)") (class "Default")
      (node (ref "R419") (pin "P$1") (pinfunction "P$1_P$1") (pintype "bidirectional"))
      (node (ref "U403") (pin "10") (pinfunction "VOB_10") (pintype "bidirectional"))
    )
    (net (code "121") (name "Net-(U404-VDDA)") (class "Default")
      (node (ref "C420") (pin "P$1") (pinfunction "P$1_P$1") (pintype "bidirectional"))
      (node (ref "D404") (pin "C") (pinfunction "C_C") (pintype "passive"))
      (node (ref "U404") (pin "16") (pinfunction "VDDA_16") (pintype "bidirectional"))
    )
    (net (code "122") (name "Net-(U404-VOA)") (class "Default")
      (node (ref "R416") (pin "P$1") (pinfunction "P$1_P$1") (pintype "bidirectional"))
      (node (ref "U404") (pin "15") (pinfunction "VOA_15") (pintype "bidirectional"))
    )
    (net (code "123") (name "Net-(U404-VOB)") (class "Default")
      (node (ref "R420") (pin "P$1") (pinfunction "P$1_P$1") (pintype "bidirectional"))
      (node (ref "U404") (pin "10") (pinfunction "VOB_10") (pintype "bidirectional"))
    )
    (net (code "124") (name "Net-(U405E-IN+)") (class "Default")
      (node (ref "C427") (pin "P$2") (pinfunction "P$2_P$2") (pintype "bidirectional"))
      (node (ref "C428") (pin "P$1") (pinfunction "P$1_P$1") (pintype "bidirectional"))
      (node (ref "R424") (pin "P$2") (pinfunction "P$2_P$2") (pintype "bidirectional"))
      (node (ref "U405") (pin "8") (pinfunction "IN+_8") (pintype "bidirectional"))
    )
    (net (code "125") (name "Net-(U405E-IN-)") (class "Default")
      (node (ref "C426") (pin "P$2") (pinfunction "P$2_P$2") (pintype "bidirectional"))
      (node (ref "C427") (pin "P$1") (pinfunction "P$1_P$1") (pintype "bidirectional"))
      (node (ref "R423") (pin "P$2") (pinfunction "P$2_P$2") (pintype "bidirectional"))
      (node (ref "U405") (pin "1") (pinfunction "IN-_1") (pintype "bidirectional"))
    )
    (net (code "126") (name "Net-(U406E-IN+)") (class "Default")
      (node (ref "C430") (pin "P$2") (pinfunction "P$2_P$2") (pintype "bidirectional"))
      (node (ref "C431") (pin "P$1") (pinfunction "P$1_P$1") (pintype "bidirectional"))
      (node (ref "R426") (pin "P$2") (pinfunction "P$2_P$2") (pintype "bidirectional"))
      (node (ref "U406") (pin "8") (pinfunction "IN+_8") (pintype "bidirectional"))
    )
    (net (code "127") (name "Net-(U406E-IN-)") (class "Default")
      (node (ref "C429") (pin "P$2") (pinfunction "P$2_P$2") (pintype "bidirectional"))
      (node (ref "C430") (pin "P$1") (pinfunction "P$1_P$1") (pintype "bidirectional"))
      (node (ref "R425") (pin "P$2") (pinfunction "P$2_P$2") (pintype "bidirectional"))
      (node (ref "U406") (pin "1") (pinfunction "IN-_1") (pintype "bidirectional"))
    )
    (net (code "128") (name "Net-(U407-AN)") (class "Default")
      (node (ref "R429") (pin "P$1") (pinfunction "P$1_P$1") (pintype "bidirectional"))
      (node (ref "U407") (pin "2") (pinfunction "AN_2") (pintype "bidirectional"))
    )
    (net (code "129") (name "Net-(U501-(CTS)GPIO4-~{CS4}-EVTCNTR)") (class "Default")
      (node (ref "JP507") (pin "1") (pinfunction "1_1") (pintype "passive"))
      (node (ref "U501") (pin "18") (pinfunction "(CTS)GPIO4-~{CS4}-EVTCNTR_18") (pintype "bidirectional"))
    )
    (net (code "130") (name "Net-(U501-(DCD)MISO)") (class "Default")
      (node (ref "JP501") (pin "1") (pinfunction "1_1") (pintype "passive"))
      (node (ref "U501") (pin "24") (pinfunction "(DCD)MISO_24") (pintype "bidirectional"))
    )
    (net (code "131") (name "Net-(U501-(DSR)GPIO0-~{CS0})") (class "Default")
      (node (ref "JP504") (pin "1") (pinfunction "1_1") (pintype "passive"))
      (node (ref "U501") (pin "22") (pinfunction "(DSR)GPIO0-~{CS0}_22") (pintype "bidirectional"))
    )
    (net (code "132") (name "Net-(U501-(DTR)MOSI)") (class "Default")
      (node (ref "JP502") (pin "1") (pinfunction "1_1") (pintype "passive"))
      (node (ref "U501") (pin "23") (pinfunction "(DTR)MOSI_23") (pintype "bidirectional"))
    )
    (net (code "133") (name "Net-(U501-(RI{slash}CLK)SCK)") (class "Default")
      (node (ref "JP503") (pin "1") (pinfunction "1_1") (pintype "passive"))
      (node (ref "U501") (pin "1") (pinfunction "(RI/CLK)SCK_1") (pintype "bidirectional"))
    )
    (net (code "134") (name "Net-(U501-(RXD)GPIO2-~{CS2})") (class "Default")
      (node (ref "JP506") (pin "1") (pinfunction "1_1") (pintype "passive"))
      (node (ref "U501") (pin "20") (pinfunction "(RXD)GPIO2-~{CS2}_20") (pintype "bidirectional"))
    )
    (net (code "135") (name "Net-(U501-(TXD)GPIO1-~{CS1})") (class "Default")
      (node (ref "JP505") (pin "1") (pinfunction "1_1") (pintype "passive"))
      (node (ref "U501") (pin "21") (pinfunction "(TXD)GPIO1-~{CS1}_21") (pintype "bidirectional"))
    )
    (net (code "136") (name "Net-(U501-VPP)") (class "Default")
      (node (ref "C503") (pin "P$1") (pinfunction "P$1_P$1") (pintype "bidirectional"))
      (node (ref "U501") (pin "16") (pinfunction "VPP_16") (pintype "bidirectional"))
    )
    (net (code "137") (name "Net-(U501-~{RST})") (class "Default")
      (node (ref "R501") (pin "P$2") (pinfunction "P$2_P$2") (pintype "bidirectional"))
      (node (ref "U501") (pin "9") (pinfunction "~{RST}_9") (pintype "bidirectional"))
    )
    (net (code "138") (name "PWM_IN") (class "Default")
      (node (ref "D504") (pin "P$3") (pinfunction "3_P$3") (pintype "bidirectional"))
      (node (ref "R504") (pin "P$2") (pinfunction "P$2_P$2") (pintype "bidirectional"))
      (node (ref "R505") (pin "P$2") (pinfunction "P$2_P$2") (pintype "bidirectional"))
      (node (ref "U102") (pin "58") (pinfunction "PWM_IN_58") (pintype "bidirectional"))
    )
    (net (code "139") (name "PWM_UX1_H") (class "Default")
      (node (ref "R405") (pin "P$2") (pinfunction "P$2_P$2") (pintype "bidirectional"))
      (node (ref "U102") (pin "39") (pinfunction "PWM_UX1_H_39") (pintype "bidirectional"))
      (node (ref "U401") (pin "1") (pinfunction "VIA_1") (pintype "bidirectional"))
    )
    (net (code "140") (name "PWM_UX1_L") (class "Default")
      (node (ref "R401") (pin "P$2") (pinfunction "P$2_P$2") (pintype "bidirectional"))
      (node (ref "U102") (pin "40") (pinfunction "PWM_UX1_L_40") (pintype "bidirectional"))
      (node (ref "U401") (pin "2") (pinfunction "VIB_2") (pintype "bidirectional"))
    )
    (net (code "141") (name "PWM_VX2_H") (class "Default")
      (node (ref "R406") (pin "P$2") (pinfunction "P$2_P$2") (pintype "bidirectional"))
      (node (ref "U102") (pin "41") (pinfunction "PWM_VX2_H_41") (pintype "bidirectional"))
      (node (ref "U402") (pin "1") (pinfunction "VIA_1") (pintype "bidirectional"))
    )
    (net (code "142") (name "PWM_VX2_L") (class "Default")
      (node (ref "R402") (pin "P$2") (pinfunction "P$2_P$2") (pintype "bidirectional"))
      (node (ref "U102") (pin "42") (pinfunction "PWM_VX2_L_42") (pintype "bidirectional"))
      (node (ref "U402") (pin "2") (pinfunction "VIB_2") (pintype "bidirectional"))
    )
    (net (code "143") (name "PWM_WY1_H") (class "Default")
      (node (ref "R407") (pin "P$2") (pinfunction "P$2_P$2") (pintype "bidirectional"))
      (node (ref "U102") (pin "46") (pinfunction "PWM_WY1_H_46") (pintype "bidirectional"))
      (node (ref "U403") (pin "1") (pinfunction "VIA_1") (pintype "bidirectional"))
    )
    (net (code "144") (name "PWM_WY1_L") (class "Default")
      (node (ref "R403") (pin "P$2") (pinfunction "P$2_P$2") (pintype "bidirectional"))
      (node (ref "U102") (pin "47") (pinfunction "PWM_WY1_L_47") (pintype "bidirectional"))
      (node (ref "U403") (pin "2") (pinfunction "VIB_2") (pintype "bidirectional"))
    )
    (net (code "145") (name "PWM_Y2_H") (class "Default")
      (node (ref "R408") (pin "P$2") (pinfunction "P$2_P$2") (pintype "bidirectional"))
      (node (ref "U102") (pin "48") (pinfunction "PWM_Y2_H_48") (pintype "bidirectional"))
      (node (ref "U404") (pin "1") (pinfunction "VIA_1") (pintype "bidirectional"))
    )
    (net (code "146") (name "PWM_Y2_L") (class "Default")
      (node (ref "R404") (pin "P$2") (pinfunction "P$2_P$2") (pintype "bidirectional"))
      (node (ref "U102") (pin "49") (pinfunction "PWM_Y2_L_49") (pintype "bidirectional"))
      (node (ref "U404") (pin "2") (pinfunction "VIB_2") (pintype "bidirectional"))
    )
    (net (code "147") (name "REF_H") (class "Default")
      (node (ref "U102") (pin "68") (pinfunction "REF_H_68") (pintype "bidirectional"))
      (node (ref "U208") (pin "5") (pinfunction "Y_5") (pintype "output"))
    )
    (net (code "148") (name "REF_L") (class "Default")
      (node (ref "U102") (pin "67") (pinfunction "REF_L_67") (pintype "bidirectional"))
      (node (ref "U208") (pin "2") (pinfunction "Y_2") (pintype "output"))
    )
    (net (code "149") (name "REF_R") (class "Default")
      (node (ref "U102") (pin "69") (pinfunction "REF_R_69") (pintype "bidirectional"))
      (node (ref "U208") (pin "7") (pinfunction "Y_7") (pintype "output"))
    )
    (net (code "150") (name "SCK") (class "Default")
      (node (ref "J501") (pin "2") (pinfunction "S_2") (pintype "passive"))
      (node (ref "JP503") (pin "2") (pinfunction "2_2") (pintype "passive"))
      (node (ref "U102") (pin "7") (pinfunction "SPI_SCK_7") (pintype "bidirectional"))
    )
    (net (code "151") (name "STEP") (class "Default")
      (node (ref "D506") (pin "P$3") (pinfunction "3_P$3") (pintype "bidirectional"))
      (node (ref "R509") (pin "P$2") (pinfunction "P$2_P$2") (pintype "bidirectional"))
      (node (ref "R510") (pin "P$2") (pinfunction "P$2_P$2") (pintype "bidirectional"))
      (node (ref "U102") (pin "57") (pinfunction "STP_57") (pintype "bidirectional"))
    )
    (net (code "152") (name "UX1") (class "Default")
      (node (ref "C417") (pin "P$2") (pinfunction "P$2_P$2") (pintype "bidirectional"))
      (node (ref "Q401") (pin "S1") (pinfunction "S1_S1") (pintype "bidirectional"))
      (node (ref "Q401") (pin "S2") (pinfunction "S1_S2") (pintype "bidirectional"))
      (node (ref "Q401") (pin "S3") (pinfunction "S1_S3") (pintype "bidirectional"))
      (node (ref "Q401") (pin "S4") (pinfunction "S1_S4") (pintype "bidirectional"))
      (node (ref "Q401") (pin "S5") (pinfunction "S1_S5") (pintype "bidirectional"))
      (node (ref "Q405") (pin "D1") (pinfunction "D1_D1") (pintype "bidirectional"))
      (node (ref "Q405") (pin "D2") (pinfunction "D1_D2") (pintype "bidirectional"))
      (node (ref "Q405") (pin "D3") (pinfunction "D1_D3") (pintype "bidirectional"))
      (node (ref "Q405") (pin "D4") (pinfunction "D1_D4") (pintype "bidirectional"))
      (node (ref "R421") (pin "1") (pinfunction "P$1_1") (pintype "bidirectional"))
      (node (ref "R421") (pin "2") (pinfunction "P$1_2") (pintype "bidirectional"))
      (node (ref "U401") (pin "14") (pinfunction "GNDA_14") (pintype "bidirectional"))
    )
    (net (code "153") (name "UX1@J401") (class "Default")
      (node (ref "J401") (pin "1") (pinfunction "S_1") (pintype "passive"))
      (node (ref "P403") (pin "H1") (pinfunction "S_H1") (pintype "passive"))
      (node (ref "P403") (pin "H10") (pinfunction "S_H10") (pintype "passive"))
      (node (ref "P403") (pin "H11") (pinfunction "S_H11") (pintype "passive"))
      (node (ref "P403") (pin "H12") (pinfunction "S_H12") (pintype "passive"))
      (node (ref "P403") (pin "H2") (pinfunction "S_H2") (pintype "passive"))
      (node (ref "P403") (pin "H3") (pinfunction "S_H3") (pintype "passive"))
      (node (ref "P403") (pin "H4") (pinfunction "S_H4") (pintype "passive"))
      (node (ref "P403") (pin "H5") (pinfunction "S_H5") (pintype "passive"))
      (node (ref "P403") (pin "H6") (pinfunction "S_H6") (pintype "passive"))
      (node (ref "P403") (pin "H7") (pinfunction "S_H7") (pintype "passive"))
      (node (ref "P403") (pin "H8") (pinfunction "S_H8") (pintype "passive"))
      (node (ref "P403") (pin "H9") (pinfunction "S_H9") (pintype "passive"))
      (node (ref "P403") (pin "PAD") (pinfunction "S_PAD") (pintype "passive"))
      (node (ref "R421") (pin "3") (pinfunction "P$2_3") (pintype "bidirectional"))
      (node (ref "R421") (pin "4") (pinfunction "P$2_4") (pintype "bidirectional"))
    )
    (net (code "154") (name "VBUS") (class "Default")
      (node (ref "R506") (pin "P$2") (pinfunction "P$2_P$2") (pintype "bidirectional"))
      (node (ref "R507") (pin "P$1") (pinfunction "P$1_P$1") (pintype "bidirectional"))
      (node (ref "U501") (pin "8") (pinfunction "VBUS_8") (pintype "bidirectional"))
    )
    (net (code "155") (name "VX2") (class "Default")
      (node (ref "C418") (pin "P$2") (pinfunction "P$2_P$2") (pintype "bidirectional"))
      (node (ref "J401") (pin "2") (pinfunction "S_2") (pintype "passive"))
      (node (ref "P401") (pin "H1") (pinfunction "S_H1") (pintype "passive"))
      (node (ref "P401") (pin "H10") (pinfunction "S_H10") (pintype "passive"))
      (node (ref "P401") (pin "H11") (pinfunction "S_H11") (pintype "passive"))
      (node (ref "P401") (pin "H12") (pinfunction "S_H12") (pintype "passive"))
      (node (ref "P401") (pin "H2") (pinfunction "S_H2") (pintype "passive"))
      (node (ref "P401") (pin "H3") (pinfunction "S_H3") (pintype "passive"))
      (node (ref "P401") (pin "H4") (pinfunction "S_H4") (pintype "passive"))
      (node (ref "P401") (pin "H5") (pinfunction "S_H5") (pintype "passive"))
      (node (ref "P401") (pin "H6") (pinfunction "S_H6") (pintype "passive"))
      (node (ref "P401") (pin "H7") (pinfunction "S_H7") (pintype "passive"))
      (node (ref "P401") (pin "H8") (pinfunction "S_H8") (pintype "passive"))
      (node (ref "P401") (pin "H9") (pinfunction "S_H9") (pintype "passive"))
      (node (ref "P401") (pin "PAD") (pinfunction "S_PAD") (pintype "passive"))
      (node (ref "Q402") (pin "S1") (pinfunction "S1_S1") (pintype "bidirectional"))
      (node (ref "Q402") (pin "S2") (pinfunction "S1_S2") (pintype "bidirectional"))
      (node (ref "Q402") (pin "S3") (pinfunction "S1_S3") (pintype "bidirectional"))
      (node (ref "Q402") (pin "S4") (pinfunction "S1_S4") (pintype "bidirectional"))
      (node (ref "Q402") (pin "S5") (pinfunction "S1_S5") (pintype "bidirectional"))
      (node (ref "Q406") (pin "D1") (pinfunction "D1_D1") (pintype "bidirectional"))
      (node (ref "Q406") (pin "D2") (pinfunction "D1_D2") (pintype "bidirectional"))
      (node (ref "Q406") (pin "D3") (pinfunction "D1_D3") (pintype "bidirectional"))
      (node (ref "Q406") (pin "D4") (pinfunction "D1_D4") (pintype "bidirectional"))
      (node (ref "U402") (pin "14") (pinfunction "GNDA_14") (pintype "bidirectional"))
    )
    (net (code "156") (name "WY1") (class "Default")
      (node (ref "C419") (pin "P$2") (pinfunction "P$2_P$2") (pintype "bidirectional"))
      (node (ref "Q403") (pin "S1") (pinfunction "S1_S1") (pintype "bidirectional"))
      (node (ref "Q403") (pin "S2") (pinfunction "S1_S2") (pintype "bidirectional"))
      (node (ref "Q403") (pin "S3") (pinfunction "S1_S3") (pintype "bidirectional"))
      (node (ref "Q403") (pin "S4") (pinfunction "S1_S4") (pintype "bidirectional"))
      (node (ref "Q403") (pin "S5") (pinfunction "S1_S5") (pintype "bidirectional"))
      (node (ref "Q407") (pin "D1") (pinfunction "D1_D1") (pintype "bidirectional"))
      (node (ref "Q407") (pin "D2") (pinfunction "D1_D2") (pintype "bidirectional"))
      (node (ref "Q407") (pin "D3") (pinfunction "D1_D3") (pintype "bidirectional"))
      (node (ref "Q407") (pin "D4") (pinfunction "D1_D4") (pintype "bidirectional"))
      (node (ref "R422") (pin "1") (pinfunction "P$1_1") (pintype "bidirectional"))
      (node (ref "R422") (pin "2") (pinfunction "P$1_2") (pintype "bidirectional"))
      (node (ref "U403") (pin "14") (pinfunction "GNDA_14") (pintype "bidirectional"))
    )
    (net (code "157") (name "WY1@J401") (class "Default")
      (node (ref "J401") (pin "3") (pinfunction "S_3") (pintype "passive"))
      (node (ref "P404") (pin "H1") (pinfunction "S_H1") (pintype "passive"))
      (node (ref "P404") (pin "H10") (pinfunction "S_H10") (pintype "passive"))
      (node (ref "P404") (pin "H11") (pinfunction "S_H11") (pintype "passive"))
      (node (ref "P404") (pin "H12") (pinfunction "S_H12") (pintype "passive"))
      (node (ref "P404") (pin "H2") (pinfunction "S_H2") (pintype "passive"))
      (node (ref "P404") (pin "H3") (pinfunction "S_H3") (pintype "passive"))
      (node (ref "P404") (pin "H4") (pinfunction "S_H4") (pintype "passive"))
      (node (ref "P404") (pin "H5") (pinfunction "S_H5") (pintype "passive"))
      (node (ref "P404") (pin "H6") (pinfunction "S_H6") (pintype "passive"))
      (node (ref "P404") (pin "H7") (pinfunction "S_H7") (pintype "passive"))
      (node (ref "P404") (pin "H8") (pinfunction "S_H8") (pintype "passive"))
      (node (ref "P404") (pin "H9") (pinfunction "S_H9") (pintype "passive"))
      (node (ref "P404") (pin "PAD") (pinfunction "S_PAD") (pintype "passive"))
      (node (ref "R422") (pin "3") (pinfunction "P$2_3") (pintype "bidirectional"))
      (node (ref "R422") (pin "4") (pinfunction "P$2_4") (pintype "bidirectional"))
    )
    (net (code "158") (name "Y2") (class "Default")
      (node (ref "C420") (pin "P$2") (pinfunction "P$2_P$2") (pintype "bidirectional"))
      (node (ref "J401") (pin "4") (pinfunction "S_4") (pintype "passive"))
      (node (ref "P402") (pin "H1") (pinfunction "S_H1") (pintype "passive"))
      (node (ref "P402") (pin "H10") (pinfunction "S_H10") (pintype "passive"))
      (node (ref "P402") (pin "H11") (pinfunction "S_H11") (pintype "passive"))
      (node (ref "P402") (pin "H12") (pinfunction "S_H12") (pintype "passive"))
      (node (ref "P402") (pin "H2") (pinfunction "S_H2") (pintype "passive"))
      (node (ref "P402") (pin "H3") (pinfunction "S_H3") (pintype "passive"))
      (node (ref "P402") (pin "H4") (pinfunction "S_H4") (pintype "passive"))
      (node (ref "P402") (pin "H5") (pinfunction "S_H5") (pintype "passive"))
      (node (ref "P402") (pin "H6") (pinfunction "S_H6") (pintype "passive"))
      (node (ref "P402") (pin "H7") (pinfunction "S_H7") (pintype "passive"))
      (node (ref "P402") (pin "H8") (pinfunction "S_H8") (pintype "passive"))
      (node (ref "P402") (pin "H9") (pinfunction "S_H9") (pintype "passive"))
      (node (ref "P402") (pin "PAD") (pinfunction "S_PAD") (pintype "passive"))
      (node (ref "Q404") (pin "S1") (pinfunction "S1_S1") (pintype "bidirectional"))
      (node (ref "Q404") (pin "S2") (pinfunction "S1_S2") (pintype "bidirectional"))
      (node (ref "Q404") (pin "S3") (pinfunction "S1_S3") (pintype "bidirectional"))
      (node (ref "Q404") (pin "S4") (pinfunction "S1_S4") (pintype "bidirectional"))
      (node (ref "Q404") (pin "S5") (pinfunction "S1_S5") (pintype "bidirectional"))
      (node (ref "Q408") (pin "D1") (pinfunction "D1_D1") (pintype "bidirectional"))
      (node (ref "Q408") (pin "D2") (pinfunction "D1_D2") (pintype "bidirectional"))
      (node (ref "Q408") (pin "D3") (pinfunction "D1_D3") (pintype "bidirectional"))
      (node (ref "Q408") (pin "D4") (pinfunction "D1_D4") (pintype "bidirectional"))
      (node (ref "U404") (pin "14") (pinfunction "GNDA_14") (pintype "bidirectional"))
    )
    (net (code "159") (name "unconnected-(J505C-S-Pad2)") (class "Default")
      (node (ref "J505") (pin "2") (pinfunction "S_2") (pintype "passive"))
    )
    (net (code "160") (name "unconnected-(U102A-ENI-Pad55)") (class "Default")
      (node (ref "U102") (pin "55") (pinfunction "ENI_55") (pintype "bidirectional"))
    )
    (net (code "161") (name "unconnected-(U102A-GPIO0-Pad70)") (class "Default")
      (node (ref "U102") (pin "70") (pinfunction "GPIO0_70") (pintype "bidirectional"))
    )
    (net (code "162") (name "unconnected-(U102A-GPIO1-Pad71)") (class "Default")
      (node (ref "U102") (pin "71") (pinfunction "GPIO1_71") (pintype "bidirectional"))
    )
    (net (code "163") (name "unconnected-(U102A-GPIO2-Pad74)") (class "Default")
      (node (ref "U102") (pin "74") (pinfunction "GPIO2_74") (pintype "bidirectional"))
    )
    (net (code "164") (name "unconnected-(U201-Pad3)") (class "Default")
      (node (ref "U201") (pin "3") (pinfunction "3_3") (pintype "bidirectional"))
    )
    (net (code "165") (name "unconnected-(U202-Pad3)") (class "Default")
      (node (ref "U202") (pin "3") (pinfunction "3_3") (pintype "bidirectional"))
    )
    (net (code "166") (name "unconnected-(U203-Pad3)") (class "Default")
      (node (ref "U203") (pin "3") (pinfunction "3_3") (pintype "bidirectional"))
    )
    (net (code "167") (name "unconnected-(U204-Pad3)") (class "Default")
      (node (ref "U204") (pin "3") (pinfunction "3_3") (pintype "bidirectional"))
    )
    (net (code "168") (name "unconnected-(U501-(GPIO2-RS485)GPIO9-~{CS9}-SUSPEND-Pad12)") (class "Default")
      (node (ref "U501") (pin "12") (pinfunction "(GPIO2-RS485)GPIO9-~{CS9}-SUSPEND_12") (pintype "bidirectional"))
    )
    (net (code "169") (name "unconnected-(U501-(GPIO3-WKUP)GPIO10-~{CS10}-~{SUSPEND}-Pad11)") (class "Default")
      (node (ref "U501") (pin "11") (pinfunction "(GPIO3-WKUP)GPIO10-~{CS10}-~{SUSPEND}_11") (pintype "bidirectional"))
    )
    (net (code "170") (name "unconnected-(U501-(RTS)GPIO3-~{CS3}-RTR-Pad19)") (class "Default")
      (node (ref "U501") (pin "19") (pinfunction "(RTS)GPIO3-~{CS3}-RTR_19") (pintype "bidirectional"))
    )
    (net (code "171") (name "unconnected-(U501-(SUSPEND)GPIO5-~{CS5}-CLKOUT-Pad17)") (class "Default")
      (node (ref "U501") (pin "17") (pinfunction "(SUSPEND)GPIO5-~{CS5}-CLKOUT_17") (pintype "bidirectional"))
    )
    (net (code "172") (name "unconnected-(U501-(~{SUSPEND})GPIO6-~{CS6}-Pad15)") (class "Default")
      (node (ref "U501") (pin "15") (pinfunction "(~{SUSPEND})GPIO6-~{CS6}_15") (pintype "bidirectional"))
    )
    (net (code "173") (name "~{CS}") (class "Default")
      (node (ref "J501") (pin "1") (pinfunction "S_1") (pintype "passive"))
      (node (ref "JP504") (pin "2") (pinfunction "2_2") (pintype "passive"))
      (node (ref "U102") (pin "6") (pinfunction "SPI_NSCS_6") (pintype "bidirectional"))
    )
  )
)
